# SCH_TEMPEC-CLOUD-SMD_2022-08-11.net
KiCad netlist of a schematic drawn in EasyEDA
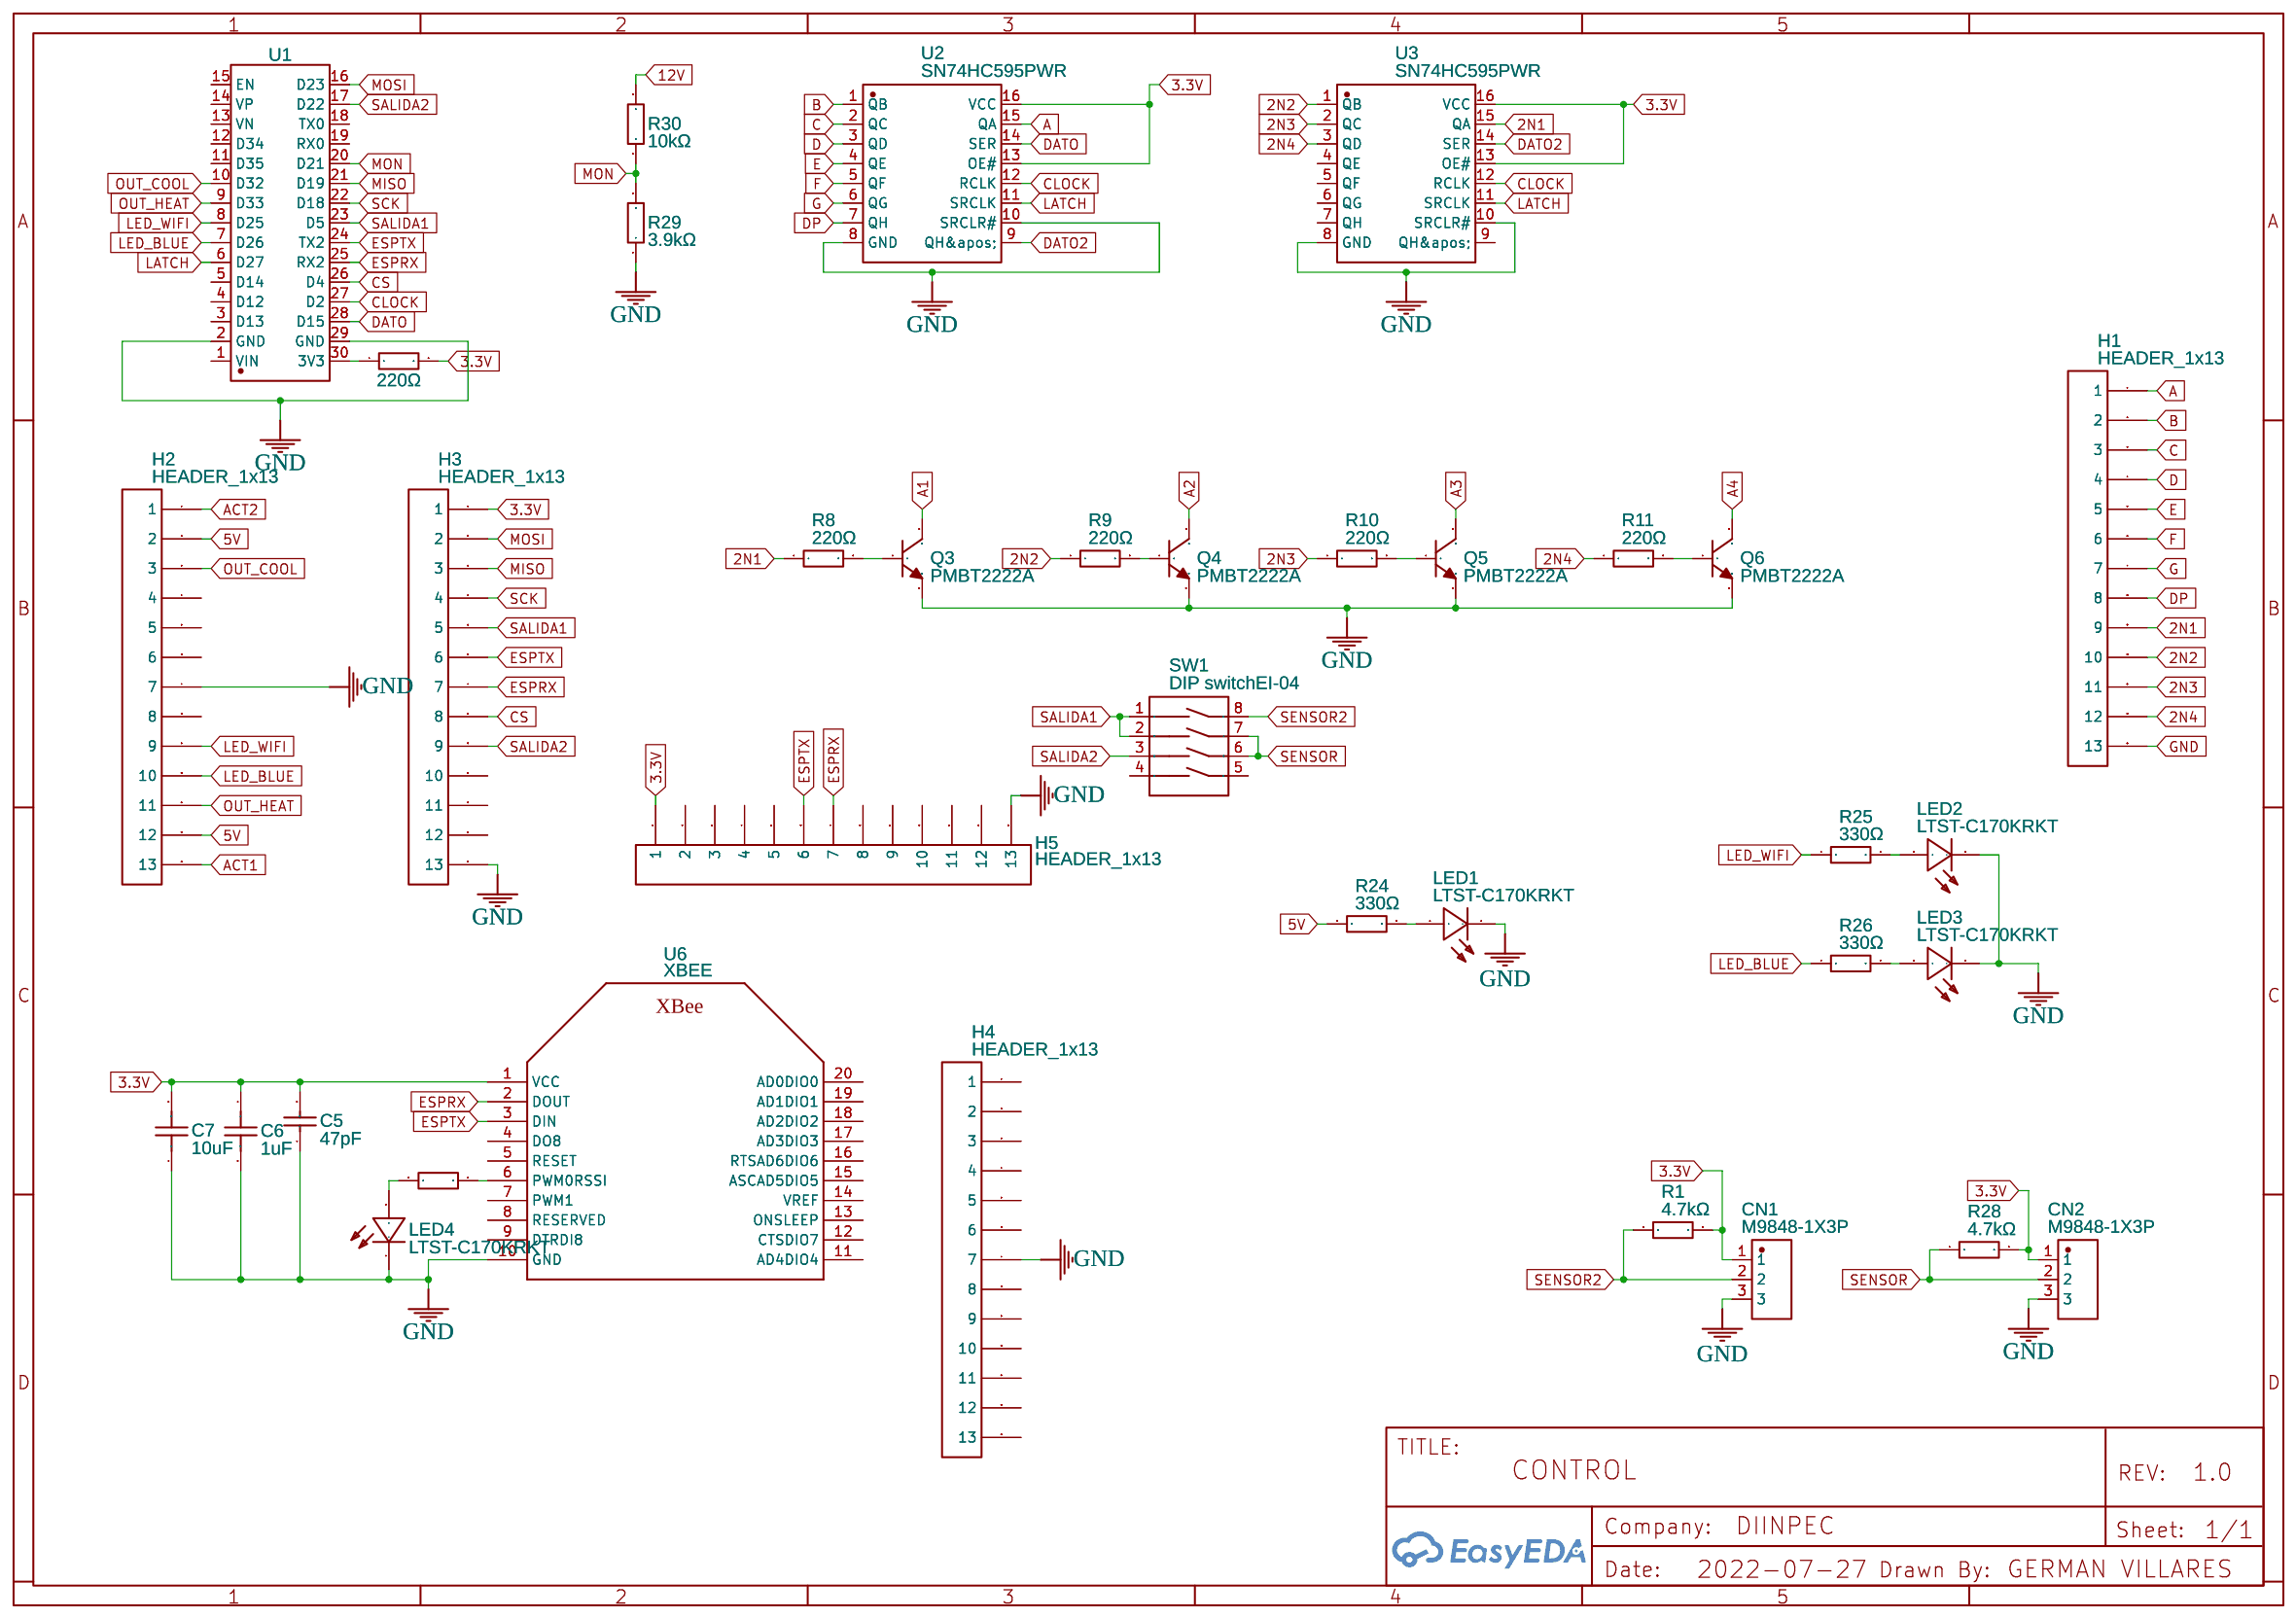
[diagram p0: CONTROL]
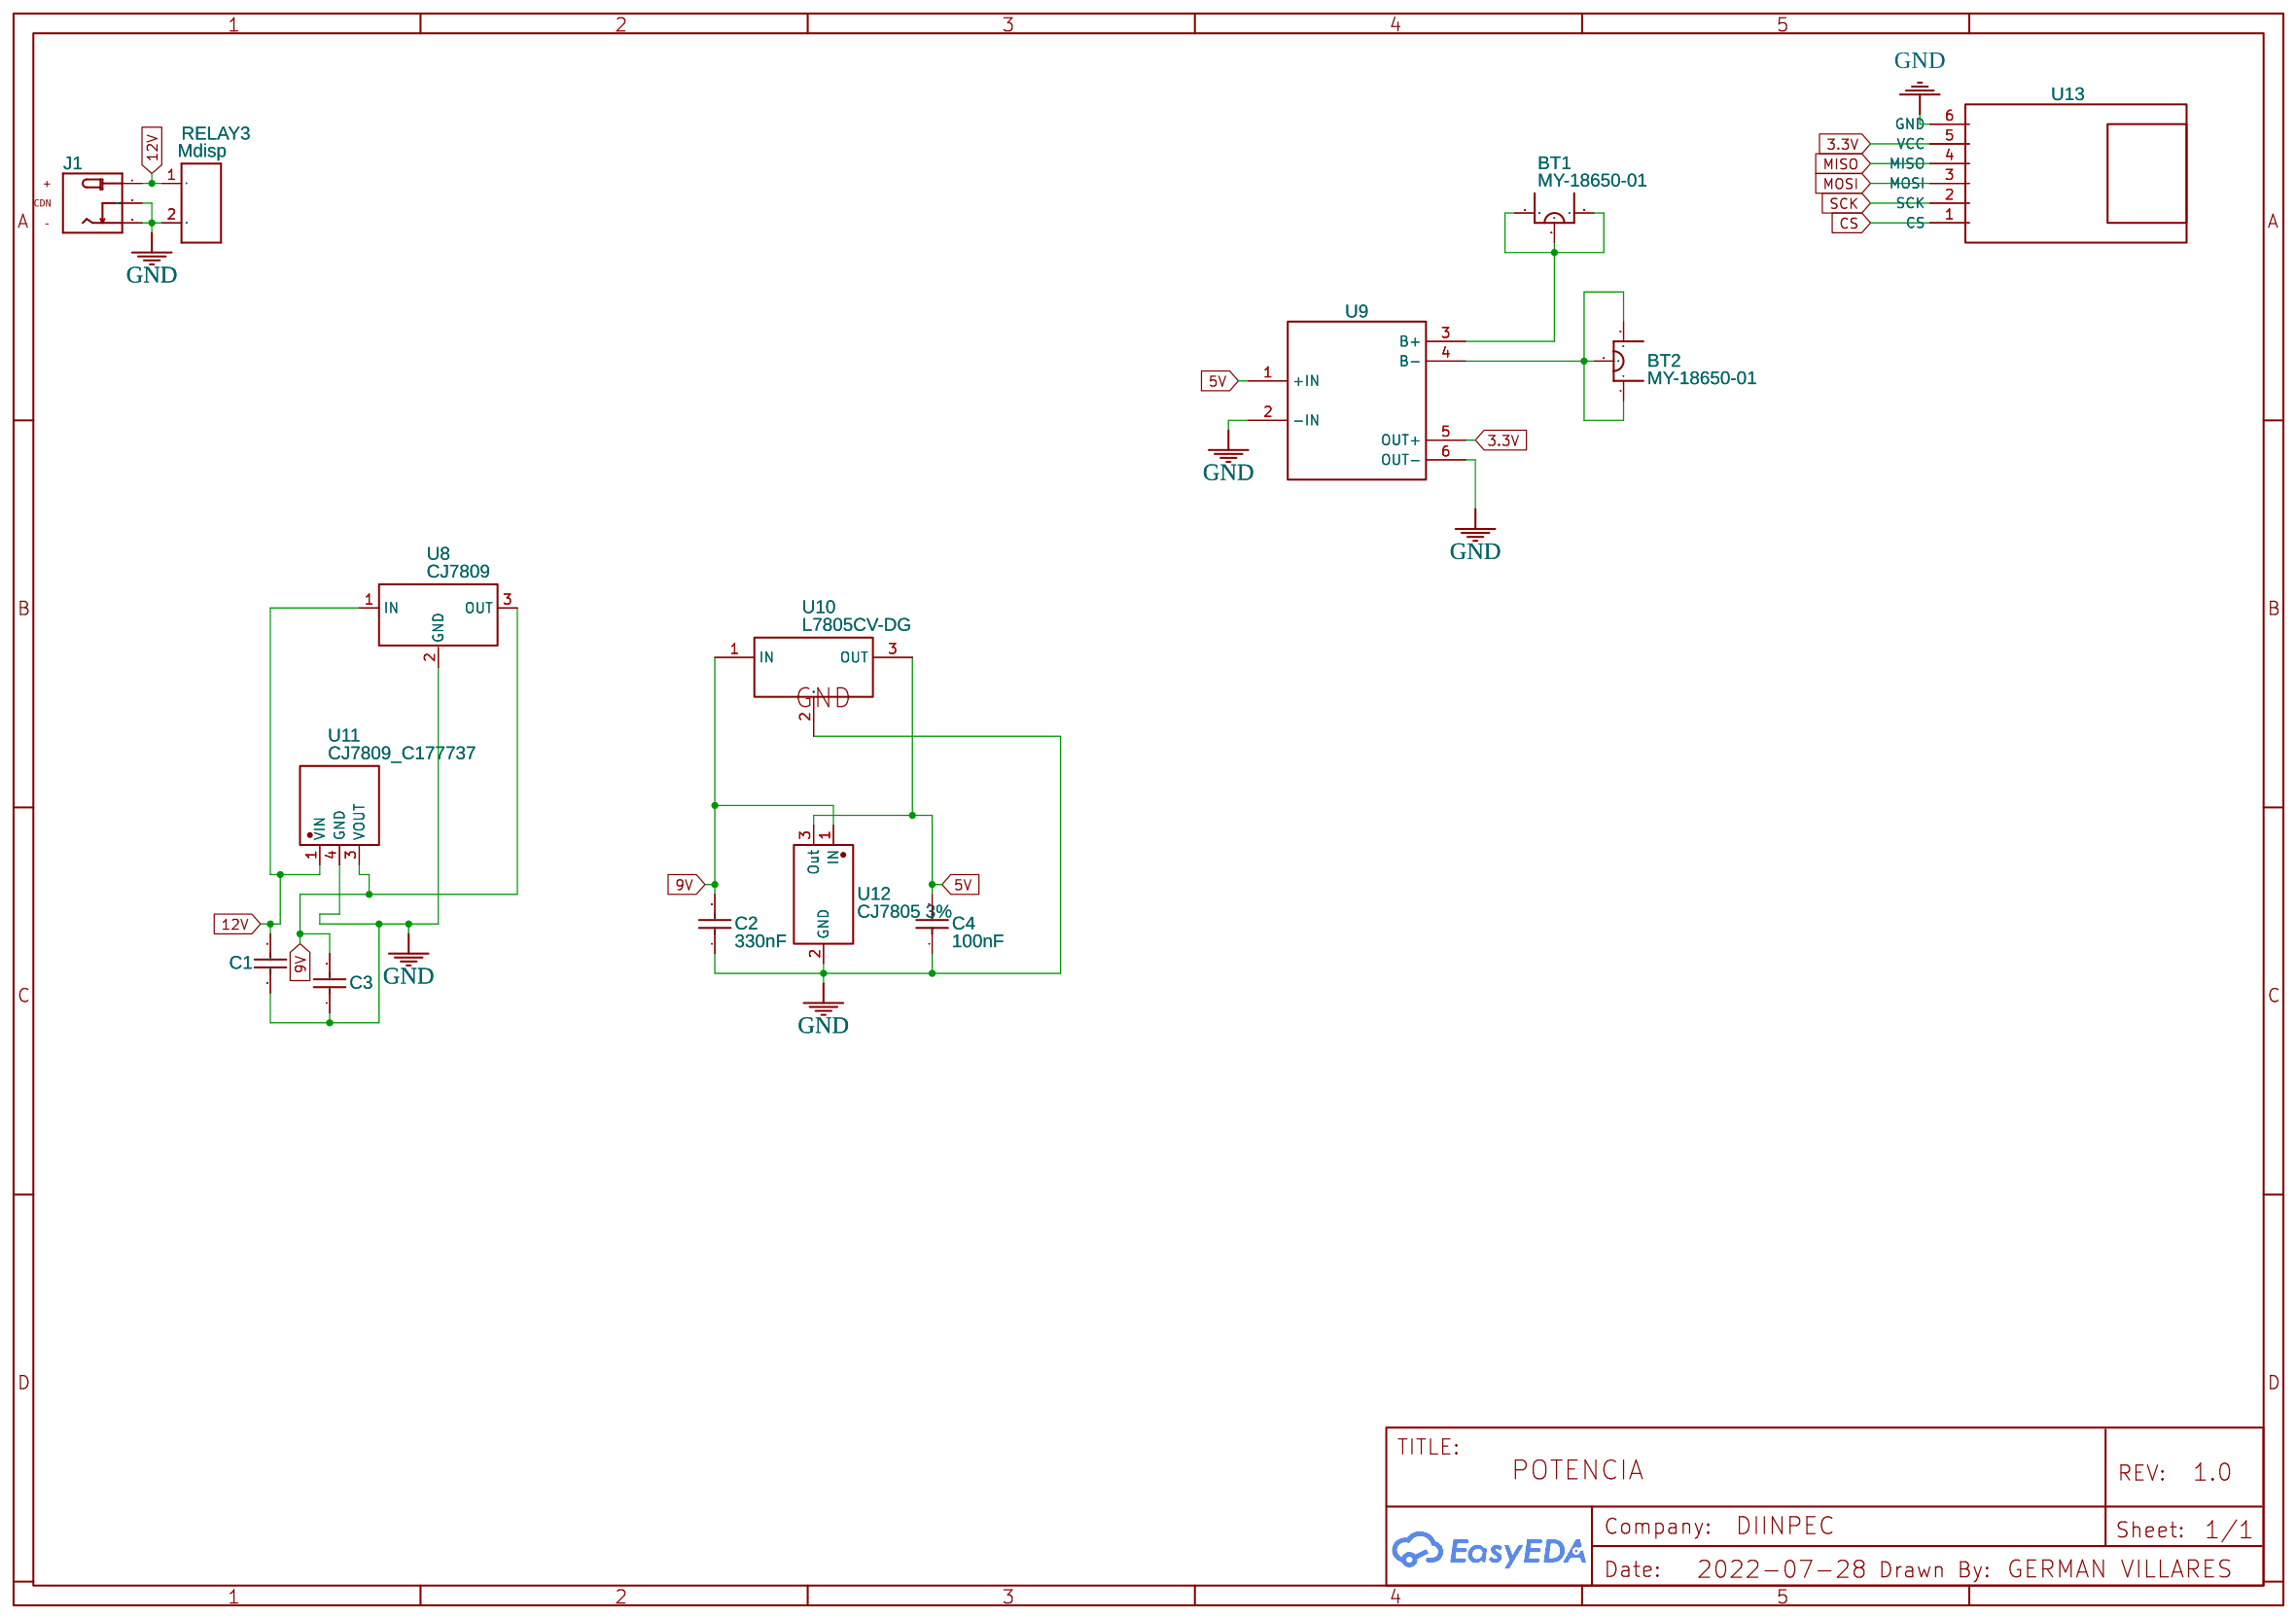
[diagram p1: POTENCIA]
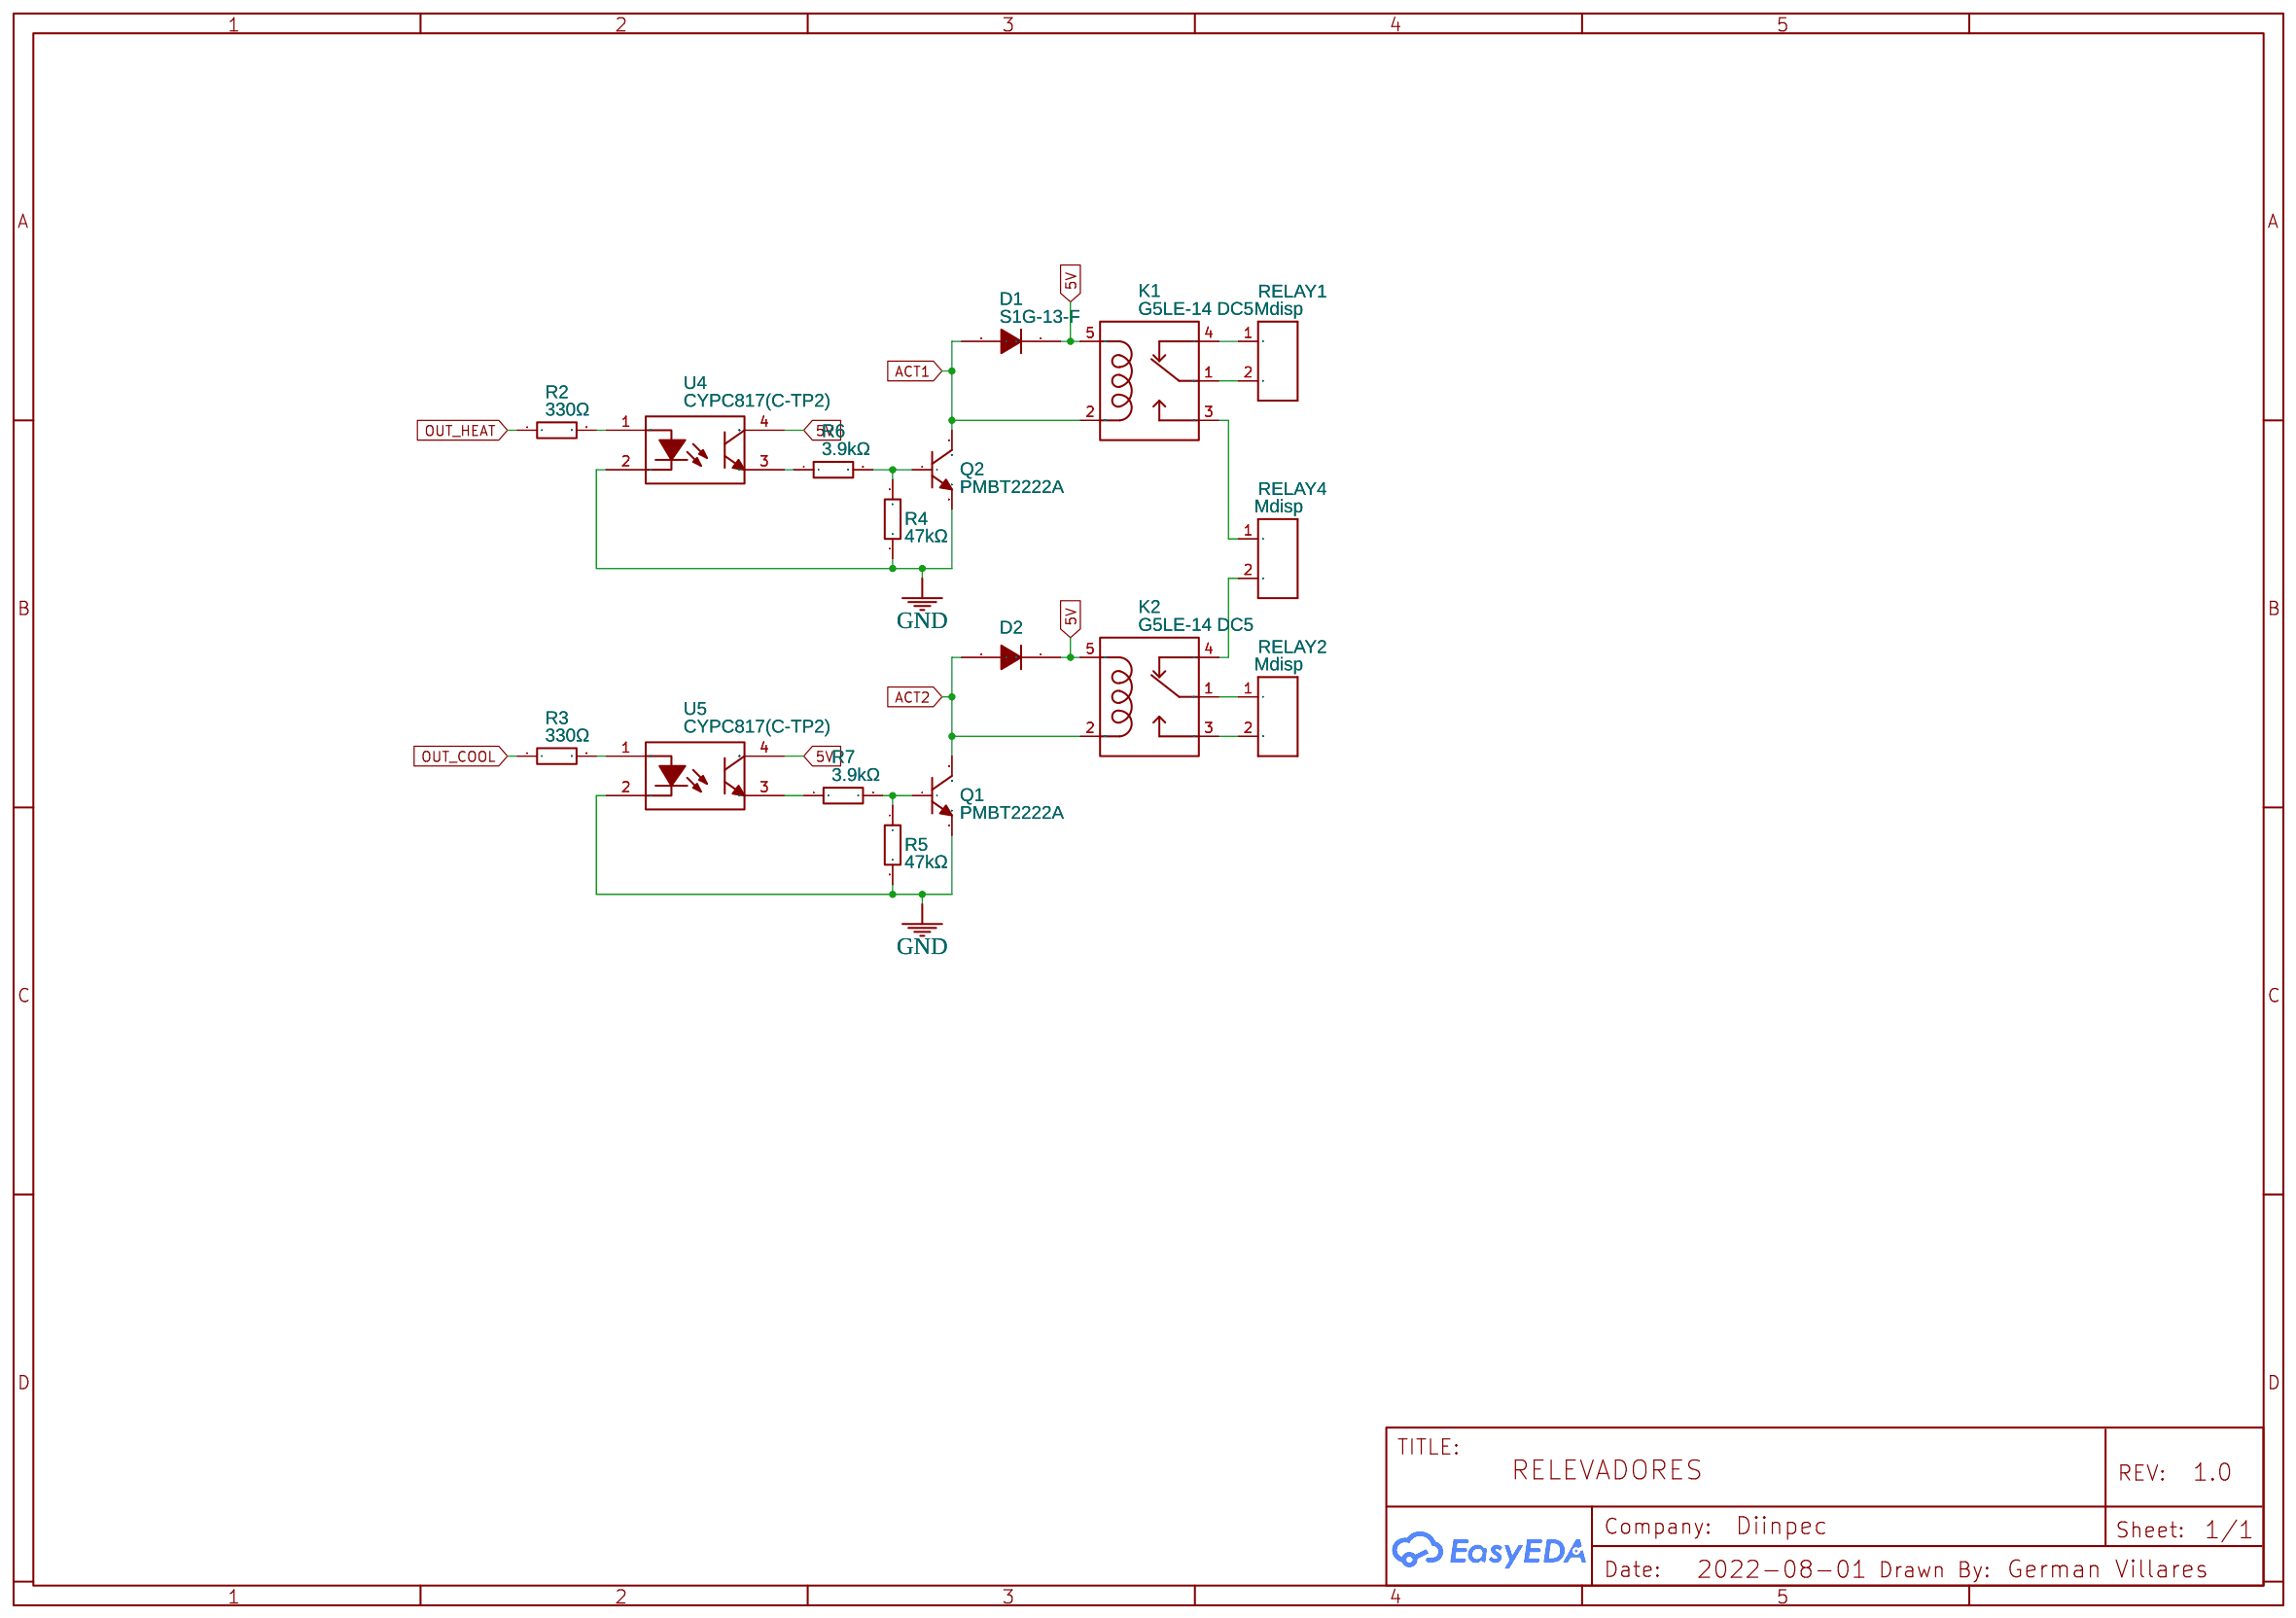
[diagram p2: Relevadores]
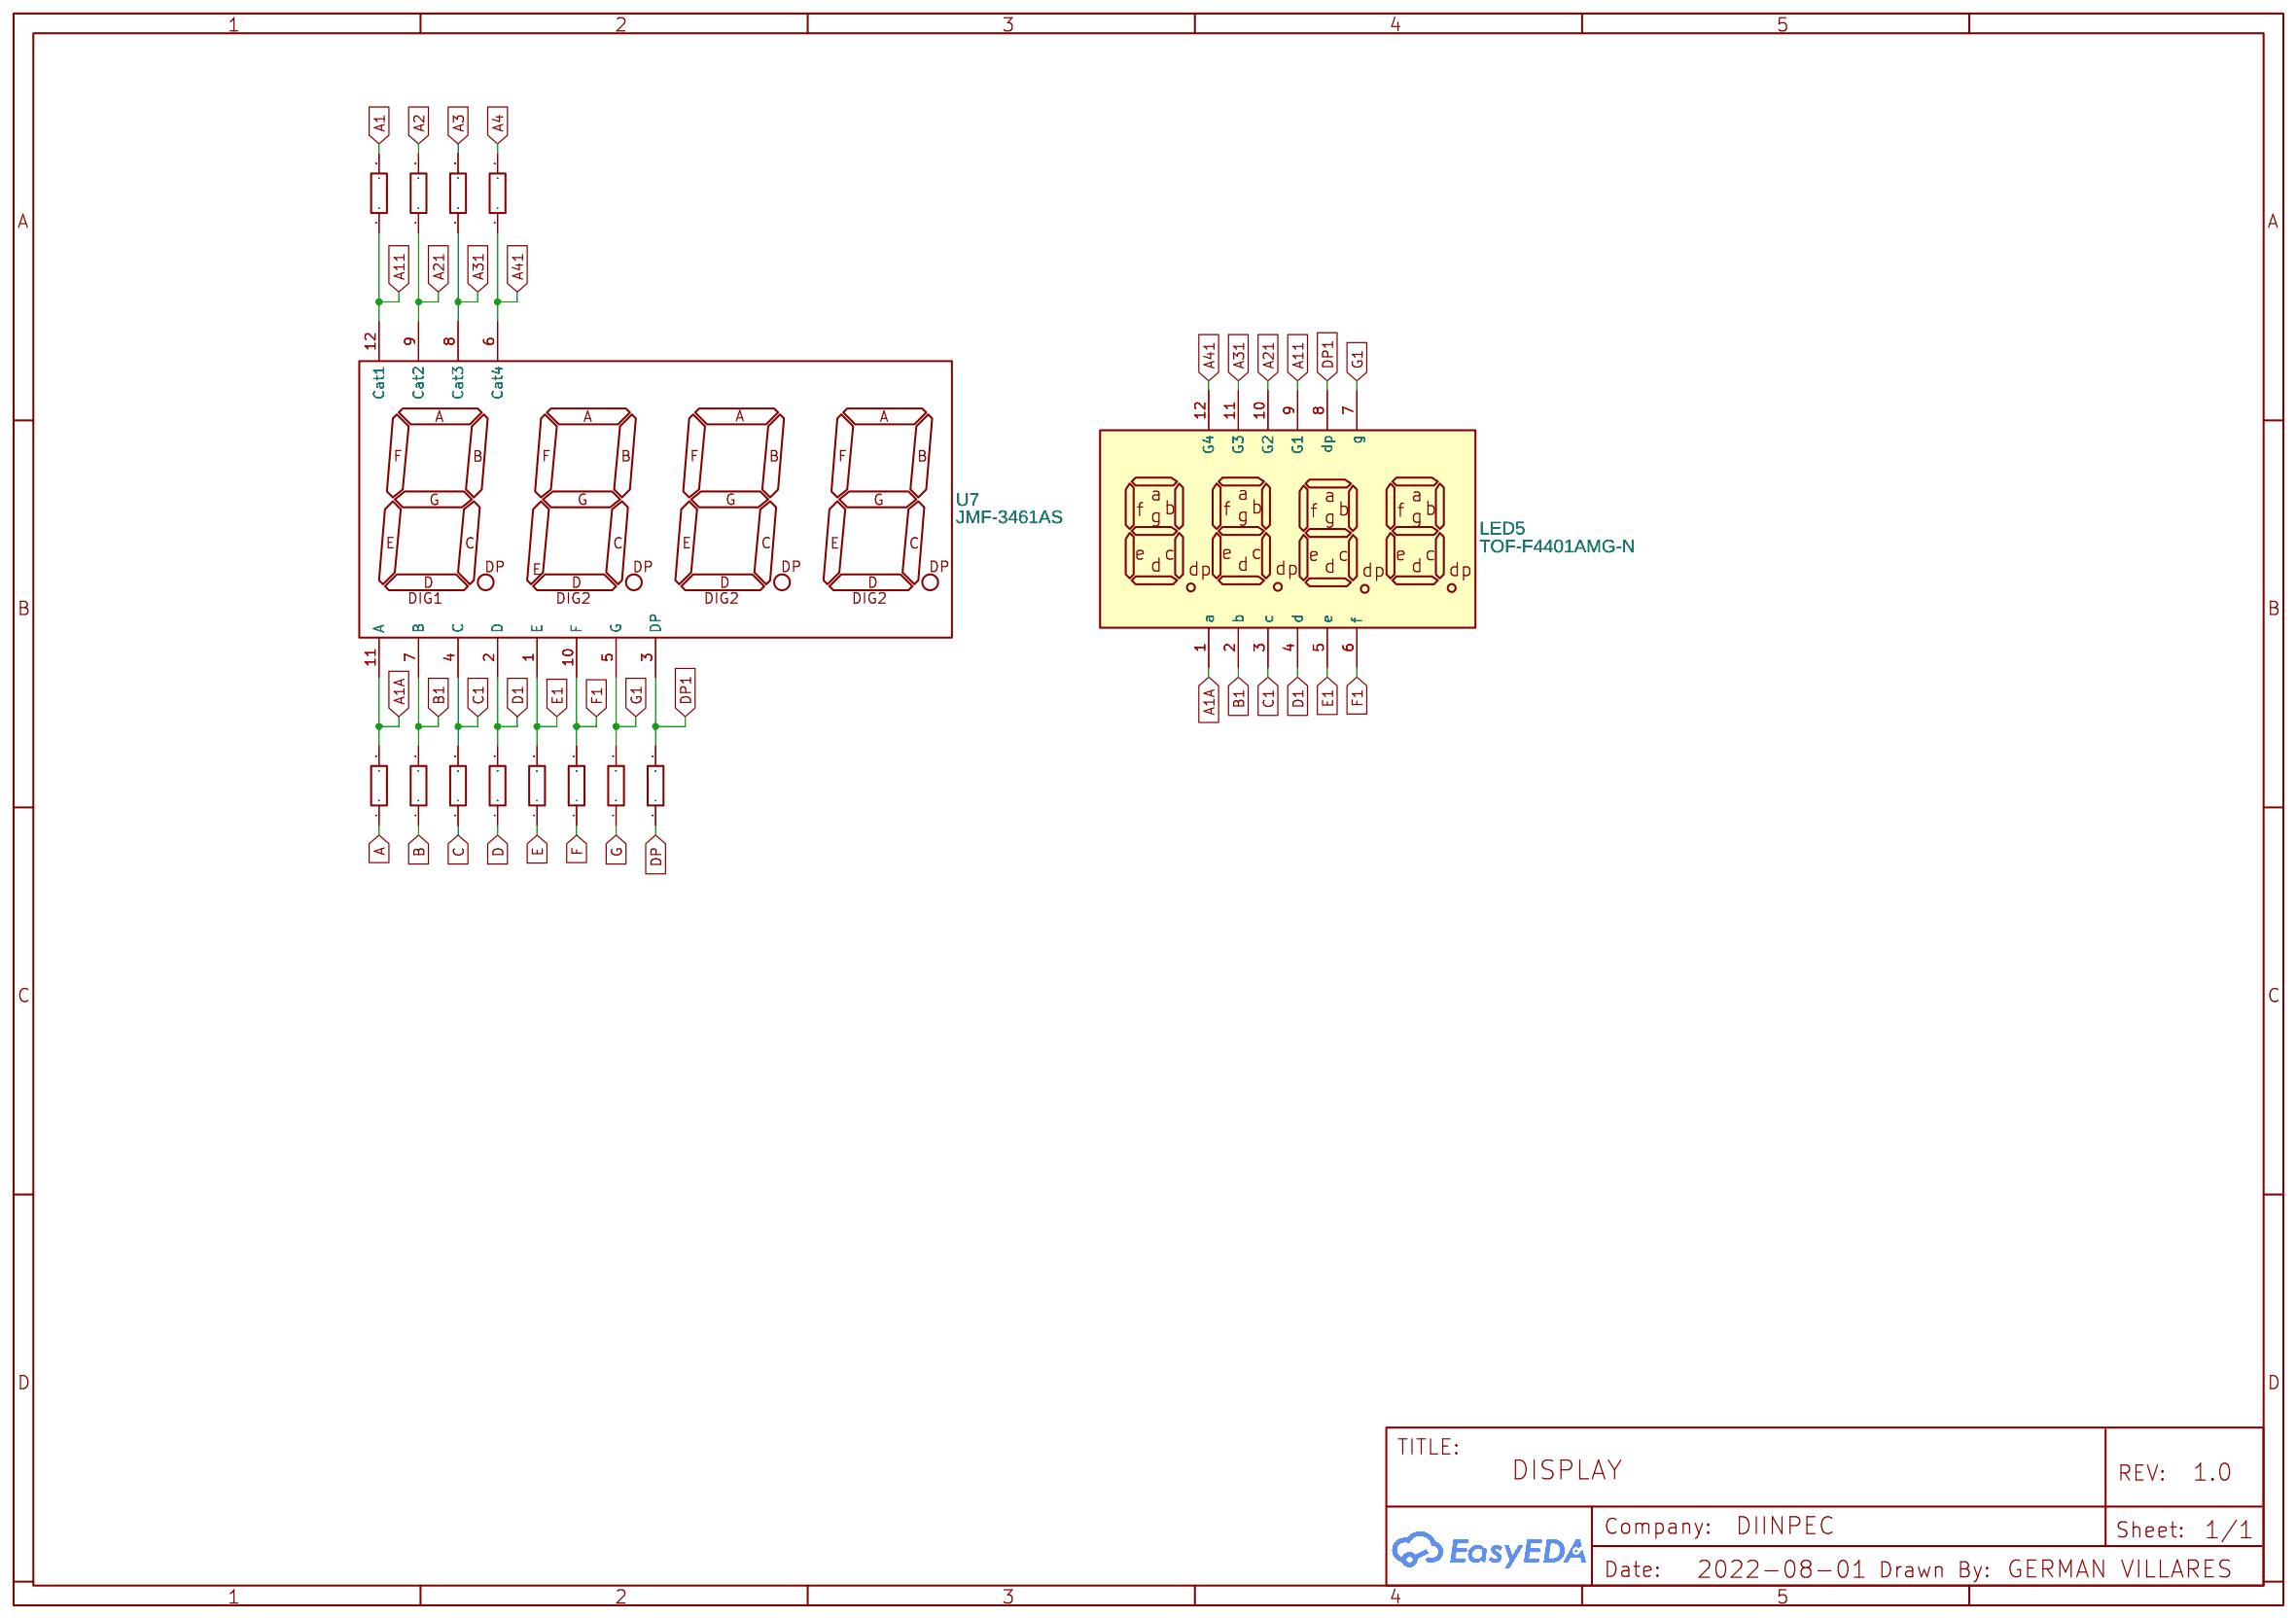
[diagram p3: DISPLAY]

(export (version "E")
  (design (tool "Eeschema 10.0.6"))
  (components
    (comp (ref "C5")
      (value "47pF")
      (fields
        (field (name "BOM_Manufacturer Part") "CC0805JRNPO9BN470")
        (field (name "BOM_Supplier Part") "C107118")
      )
      (libsource (lib "") (part "CC0805JRNPO9BN470"))
    )
    (comp (ref "C6")
      (value "1uF")
      (fields
        (field (name "BOM_Manufacturer Part") "TCC0805X7R105K500DTS")
        (field (name "BOM_Supplier Part") "C344178")
      )
      (libsource (lib "") (part "TCC0805X7R105K500DTS"))
    )
    (comp (ref "C7")
      (value "10uF")
      (fields
        (field (name "BOM_Manufacturer Part") "CL31B106KBHNNNE")
        (field (name "BOM_Supplier Part") "C89632")
      )
      (libsource (lib "") (part "CL31B106KBHNNNE"))
    )
    (comp (ref "CN1")
      (value "M9848-1X3P")
      (fields
        (field (name "BOM_Manufacturer Part") "M9848-1x3P")
        (field (name "BOM_Supplier Part") "C492604")
      )
      (libsource (lib "") (part "M9848-1X3P"))
    )
    (comp (ref "CN2")
      (value "M9848-1X3P")
      (fields
        (field (name "BOM_Manufacturer Part") "M9848-1x3P")
        (field (name "BOM_Supplier Part") "C492604")
      )
      (libsource (lib "") (part "M9848-1X3P"))
    )
    (comp (ref "H1") (value "HEADER_1x13") (libsource (lib "") (part "HEADER_1x13")))
    (comp (ref "H2") (value "HEADER_1x13") (libsource (lib "") (part "HEADER_1x13")))
    (comp (ref "H3") (value "HEADER_1x13") (libsource (lib "") (part "HEADER_1x13")))
    (comp (ref "H4") (value "HEADER_1x13") (libsource (lib "") (part "HEADER_1x13")))
    (comp (ref "H5") (value "HEADER_1x13") (libsource (lib "") (part "HEADER_1x13_1")))
    (comp (ref "LED1")
      (value "LTST-C170KRKT")
      (fields (field (name "BOM_Supplier Part") "C94868"))
      (libsource (lib "") (part "LTST-C170KRKT"))
    )
    (comp (ref "LED2")
      (value "LTST-C170KRKT")
      (fields (field (name "BOM_Supplier Part") "C94868"))
      (libsource (lib "") (part "LTST-C170KRKT"))
    )
    (comp (ref "LED3")
      (value "LTST-C170KRKT")
      (fields (field (name "BOM_Supplier Part") "C94868"))
      (libsource (lib "") (part "LTST-C170KRKT"))
    )
    (comp (ref "LED4")
      (value "LTST-C170KRKT")
      (fields (field (name "BOM_Supplier Part") "C94868"))
      (libsource (lib "") (part "LTST-C170KRKT_1"))
    )
    (comp (ref "Q3")
      (value "PMBT2222A")
      (fields (field (name "BOM_Supplier Part") "C23869"))
      (libsource (lib "") (part "PMBT2222A"))
    )
    (comp (ref "Q4")
      (value "PMBT2222A")
      (fields (field (name "BOM_Supplier Part") "C23869"))
      (libsource (lib "") (part "PMBT2222A"))
    )
    (comp (ref "Q5")
      (value "PMBT2222A")
      (fields (field (name "BOM_Supplier Part") "C23869"))
      (libsource (lib "") (part "PMBT2222A"))
    )
    (comp (ref "Q6")
      (value "PMBT2222A")
      (fields (field (name "BOM_Supplier Part") "C23869"))
      (libsource (lib "") (part "PMBT2222A"))
    )
    (comp (ref "R1")
      (value "4.7kΩ")
      (fields
        (field (name "BOM_Manufacturer Part") "RS-06K472JT")
        (field (name "BOM_Supplier Part") "C118074")
      )
      (libsource (lib "") (part "RS-06K472JT"))
    )
    (comp (ref "R8")
      (value "220Ω")
      (fields
        (field (name "BOM_Manufacturer Part") "CR1206F42200G")
        (field (name "BOM_Supplier Part") "C102128")
      )
      (libsource (lib "") (part "CR1206F42200G"))
    )
    (comp (ref "R9")
      (value "220Ω")
      (fields
        (field (name "BOM_Manufacturer Part") "CR1206F42200G")
        (field (name "BOM_Supplier Part") "C102128")
      )
      (libsource (lib "") (part "CR1206F42200G"))
    )
    (comp (ref "R10")
      (value "220Ω")
      (fields
        (field (name "BOM_Manufacturer Part") "CR1206F42200G")
        (field (name "BOM_Supplier Part") "C102128")
      )
      (libsource (lib "") (part "CR1206F42200G"))
    )
    (comp (ref "R11")
      (value "220Ω")
      (fields
        (field (name "BOM_Manufacturer Part") "CR1206F42200G")
        (field (name "BOM_Supplier Part") "C102128")
      )
      (libsource (lib "") (part "CR1206F42200G"))
    )
    (comp (ref "R24")
      (value "330Ω")
      (fields
        (field (name "BOM_Manufacturer Part") "1206W4F3300T5E")
        (field (name "BOM_Supplier Part") "C17930")
      )
      (libsource (lib "") (part "1206W4F3300T5E"))
    )
    (comp (ref "R25")
      (value "330Ω")
      (fields
        (field (name "BOM_Manufacturer Part") "1206W4F3300T5E")
        (field (name "BOM_Supplier Part") "C17930")
      )
      (libsource (lib "") (part "1206W4F3300T5E"))
    )
    (comp (ref "R26")
      (value "330Ω")
      (fields
        (field (name "BOM_Manufacturer Part") "1206W4F3300T5E")
        (field (name "BOM_Supplier Part") "C17930")
      )
      (libsource (lib "") (part "1206W4F3300T5E"))
    )
    (comp (ref "R27")
      (value "220Ω")
      (fields
        (field (name "BOM_Manufacturer Part") "CR1206F42200G")
        (field (name "BOM_Supplier Part") "C102128")
      )
      (libsource (lib "") (part "CR1206F42200G"))
    )
    (comp (ref "R28")
      (value "4.7kΩ")
      (fields
        (field (name "BOM_Manufacturer Part") "RS-06K472JT")
        (field (name "BOM_Supplier Part") "C118074")
      )
      (libsource (lib "") (part "RS-06K472JT"))
    )
    (comp (ref "R29")
      (value "3.9kΩ")
      (fields
        (field (name "BOM_Manufacturer Part") "RMC12063.9K5%N")
        (field (name "BOM_Supplier Part") "C269606")
      )
      (libsource (lib "") (part "RMC12063.9K5%N"))
    )
    (comp (ref "R30")
      (value "10kΩ")
      (fields
        (field (name "BOM_Manufacturer Part") "RTT061002FTP")
        (field (name "BOM_Supplier Part") "C104595")
      )
      (libsource (lib "") (part "RTT061002FTP"))
    )
    (comp (ref "R31")
      (value "330Ω")
      (fields
        (field (name "BOM_Manufacturer Part") "1206W4F3300T5E")
        (field (name "BOM_Supplier Part") "C17930")
      )
      (libsource (lib "") (part "1206W4F3300T5E_1"))
    )
    (comp (ref "SW1")
      (value "DIP switchEI-04")
      (fields (field (name "BOM_Supplier Part") "C99987"))
      (libsource (lib "") (part "DIP switchEI-04"))
    )
    (comp (ref "U1")
      (value "ESP32-WROOM-32-DEV KIT C")
      (libsource (lib "") (part "ESP32-WROOM-32-DEV KIT C"))
    )
    (comp (ref "U2")
      (value "SN74HC595PWR")
      (fields (field (name "BOM_Supplier Part") "C273642"))
      (libsource (lib "") (part "SN74HC595PWR"))
    )
    (comp (ref "U3")
      (value "SN74HC595PWR")
      (fields (field (name "BOM_Supplier Part") "C273642"))
      (libsource (lib "") (part "SN74HC595PWR"))
    )
    (comp (ref "U6") (value "XBEE") (libsource (lib "") (part "Unknown_335_-240")))
    (comp (ref "BT1")
      (value "MY-18650-01")
      (fields (field (name "BOM_Supplier Part") "C2979183"))
      (libsource (lib "") (part "MY-18650-01_1"))
    )
    (comp (ref "BT2")
      (value "MY-18650-01")
      (fields (field (name "BOM_Supplier Part") "C2979183"))
      (libsource (lib "") (part "MY-18650-01"))
    )
    (comp (ref "C1")
      (value "330nF")
      (fields
        (field (name "BOM_Manufacturer Part") "0805F334M500NT")
        (field (name "BOM_Supplier Part") "C1775")
      )
      (libsource (lib "") (part "0805F334M500NT"))
    )
    (comp (ref "C2")
      (value "330nF")
      (fields
        (field (name "BOM_Manufacturer Part") "0805F334M500NT")
        (field (name "BOM_Supplier Part") "C1775")
      )
      (libsource (lib "") (part "0805F334M500NT"))
    )
    (comp (ref "C3")
      (value "100nF")
      (fields
        (field (name "BOM_Manufacturer Part") "CL21B104JBCNNNC")
        (field (name "BOM_Supplier Part") "C62912")
      )
      (libsource (lib "") (part "CL21B104JBCNNNC"))
    )
    (comp (ref "C4")
      (value "100nF")
      (fields
        (field (name "BOM_Manufacturer Part") "CL21B104JBCNNNC")
        (field (name "BOM_Supplier Part") "C62912")
      )
      (libsource (lib "") (part "CL21B104JBCNNNC"))
    )
    (comp (ref "J1")
      (value "CONN-POWER-JACK-2.1MM_DC-005_")
      (libsource (lib "") (part "CONN-POWER-JACK-2.1MM_DC-005_"))
    )
    (comp (ref "RELAY3")
      (value "Mdisp")
      (fields (field (name "BOM_Manufacturer Part") "?"))
      (libsource (lib "") (part "Unknown_90_-710"))
    )
    (comp (ref "U8")
      (value "CJ7809")
      (fields (field (name "BOM_Supplier Part") "C105445"))
      (libsource (lib "") (part "CJ7809"))
    )
    (comp (ref "U9") (value "TP4056 MODULE D0") (libsource (lib "") (part "TP4056 MODULE D0")))
    (comp (ref "U10")
      (value "L7805CV-DG")
      (fields (field (name "BOM_Supplier Part") "C3795"))
      (libsource (lib "") (part "L7805CV-DG"))
    )
    (comp (ref "U11")
      (value "CJ7809_C177737")
      (fields (field (name "BOM_Manufacturer Part") "CJ7809") (field (name "BOM_Supplier Part") "C177737"))
      (libsource (lib "") (part "CJ7809_C177737"))
    )
    (comp (ref "U12")
      (value "CJ7805 3%")
      (fields (field (name "BOM_Supplier Part") "C21706"))
      (libsource (lib "") (part "CJ7805 3%"))
    )
    (comp (ref "U13") (value "MicroSDCardAdapter") (libsource (lib "") (part "MicroSDCardAdapter")))
    (comp (ref "D1")
      (value "S1G-13-F")
      (fields (field (name "BOM_Supplier Part") "C85102"))
      (libsource (lib "") (part "S1G-13-F"))
    )
    (comp (ref "D2")
      (value "S1G-13-F")
      (fields (field (name "BOM_Supplier Part") "C85102"))
      (libsource (lib "") (part "S1G-13-F"))
    )
    (comp (ref "K1")
      (value "G5LE-14 DC5")
      (fields (field (name "BOM_Supplier Part") "C152709"))
      (libsource (lib "") (part "Unknown_580_-620"))
    )
    (comp (ref "K2")
      (value "G5LE-14 DC5")
      (fields (field (name "BOM_Supplier Part") "C152709"))
      (libsource (lib "") (part "Unknown_580_-460"))
    )
    (comp (ref "Q1")
      (value "PMBT2222A")
      (fields (field (name "BOM_Supplier Part") "C23869"))
      (libsource (lib "") (part "PMBT2222A"))
    )
    (comp (ref "Q2")
      (value "PMBT2222A")
      (fields (field (name "BOM_Supplier Part") "C23869"))
      (libsource (lib "") (part "PMBT2222A"))
    )
    (comp (ref "R2")
      (value "330Ω")
      (fields
        (field (name "BOM_Manufacturer Part") "1206W4F3300T5E")
        (field (name "BOM_Supplier Part") "C17930")
      )
      (libsource (lib "") (part "1206W4F3300T5E"))
    )
    (comp (ref "R3")
      (value "330Ω")
      (fields
        (field (name "BOM_Manufacturer Part") "1206W4F3300T5E")
        (field (name "BOM_Supplier Part") "C17930")
      )
      (libsource (lib "") (part "1206W4F3300T5E"))
    )
    (comp (ref "R4")
      (value "47kΩ")
      (fields
        (field (name "BOM_Manufacturer Part") "RTT06473JTP")
        (field (name "BOM_Supplier Part") "C104822")
      )
      (libsource (lib "") (part "RTT06473JTP"))
    )
    (comp (ref "R5")
      (value "47kΩ")
      (fields
        (field (name "BOM_Manufacturer Part") "RTT06473JTP")
        (field (name "BOM_Supplier Part") "C104822")
      )
      (libsource (lib "") (part "RTT06473JTP_1"))
    )
    (comp (ref "R6")
      (value "3.9kΩ")
      (fields
        (field (name "BOM_Manufacturer Part") "RMC12063.9K5%N")
        (field (name "BOM_Supplier Part") "C269606")
      )
      (libsource (lib "") (part "RMC12063.9K5%N"))
    )
    (comp (ref "R7")
      (value "3.9kΩ")
      (fields
        (field (name "BOM_Manufacturer Part") "RMC12063.9K5%N")
        (field (name "BOM_Supplier Part") "C269606")
      )
      (libsource (lib "") (part "RMC12063.9K5%N"))
    )
    (comp (ref "RELAY1")
      (value "Mdisp")
      (fields (field (name "BOM_Manufacturer Part") "?"))
      (libsource (lib "") (part "Unknown_635_-630"))
    )
    (comp (ref "RELAY2")
      (value "Mdisp")
      (fields (field (name "BOM_Manufacturer Part") "?"))
      (libsource (lib "") (part "Unknown_635_-450"))
    )
    (comp (ref "RELAY4")
      (value "Mdisp")
      (fields (field (name "BOM_Manufacturer Part") "?"))
      (libsource (lib "") (part "Unknown_635_-530"))
    )
    (comp (ref "U4")
      (value "CYPC817(C-TP2)")
      (fields (field (name "BOM_Supplier Part") "C385058"))
      (libsource (lib "") (part "CYPC817(C-TP2)"))
    )
    (comp (ref "U5")
      (value "CYPC817(C-TP2)")
      (fields (field (name "BOM_Supplier Part") "C385058"))
      (libsource (lib "") (part "CYPC817(C-TP2)"))
    )
    (comp (ref "LED5")
      (value "TOF-F4401AMG-N")
      (fields (field (name "BOM_Supplier Part") "C325426"))
      (libsource (lib "") (part "TOF-F4401AMG-N"))
    )
    (comp (ref "R12")
      (value "220Ω")
      (fields
        (field (name "BOM_Manufacturer Part") "AECR1206F220RK9")
        (field (name "BOM_Supplier Part") "C352117")
      )
      (libsource (lib "") (part "AECR1206F220RK9"))
    )
    (comp (ref "R13")
      (value "220Ω")
      (fields
        (field (name "BOM_Manufacturer Part") "AECR1206F220RK9")
        (field (name "BOM_Supplier Part") "C352117")
      )
      (libsource (lib "") (part "AECR1206F220RK9"))
    )
    (comp (ref "R14")
      (value "220Ω")
      (fields
        (field (name "BOM_Manufacturer Part") "AECR1206F220RK9")
        (field (name "BOM_Supplier Part") "C352117")
      )
      (libsource (lib "") (part "AECR1206F220RK9"))
    )
    (comp (ref "R15")
      (value "220Ω")
      (fields
        (field (name "BOM_Manufacturer Part") "AECR1206F220RK9")
        (field (name "BOM_Supplier Part") "C352117")
      )
      (libsource (lib "") (part "AECR1206F220RK9"))
    )
    (comp (ref "R16")
      (value "220Ω")
      (fields
        (field (name "BOM_Manufacturer Part") "AECR1206F220RK9")
        (field (name "BOM_Supplier Part") "C352117")
      )
      (libsource (lib "") (part "AECR1206F220RK9"))
    )
    (comp (ref "R17")
      (value "220Ω")
      (fields
        (field (name "BOM_Manufacturer Part") "AECR1206F220RK9")
        (field (name "BOM_Supplier Part") "C352117")
      )
      (libsource (lib "") (part "AECR1206F220RK9"))
    )
    (comp (ref "R18")
      (value "220Ω")
      (fields
        (field (name "BOM_Manufacturer Part") "AECR1206F220RK9")
        (field (name "BOM_Supplier Part") "C352117")
      )
      (libsource (lib "") (part "AECR1206F220RK9"))
    )
    (comp (ref "R19")
      (value "220Ω")
      (fields
        (field (name "BOM_Manufacturer Part") "AECR1206F220RK9")
        (field (name "BOM_Supplier Part") "C352117")
      )
      (libsource (lib "") (part "AECR1206F220RK9"))
    )
    (comp (ref "R20")
      (value "220Ω")
      (fields
        (field (name "BOM_Manufacturer Part") "AECR1206F220RK9")
        (field (name "BOM_Supplier Part") "C352117")
      )
      (libsource (lib "") (part "AECR1206F220RK9"))
    )
    (comp (ref "R21")
      (value "220Ω")
      (fields
        (field (name "BOM_Manufacturer Part") "AECR1206F220RK9")
        (field (name "BOM_Supplier Part") "C352117")
      )
      (libsource (lib "") (part "AECR1206F220RK9"))
    )
    (comp (ref "R22")
      (value "220Ω")
      (fields
        (field (name "BOM_Manufacturer Part") "AECR1206F220RK9")
        (field (name "BOM_Supplier Part") "C352117")
      )
      (libsource (lib "") (part "AECR1206F220RK9"))
    )
    (comp (ref "R23")
      (value "220Ω")
      (fields
        (field (name "BOM_Manufacturer Part") "AECR1206F220RK9")
        (field (name "BOM_Supplier Part") "C352117")
      )
      (libsource (lib "") (part "AECR1206F220RK9"))
    )
    (comp (ref "U7")
      (value "JMF-3461AS")
      (fields (field (name "BOM_Manufacturer Part") "3461AS"))
      (libsource (lib "") (part "JMF-3461AS"))
    )
  )
  (nets
    (net (code "1") (name "2N1") (class "Default")
      (node (ref "H1") (pin "9") (pinfunction "9_9") (pintype "unspecified"))
      (node (ref "R8") (pin "1") (pinfunction "1_1") (pintype "input"))
      (node (ref "U3") (pin "15") (pinfunction "QA_15") (pintype "unspecified"))
    )
    (net (code "2") (name "2N2") (class "Default")
      (node (ref "H1") (pin "10") (pinfunction "10_10") (pintype "unspecified"))
      (node (ref "R9") (pin "1") (pinfunction "1_1") (pintype "input"))
      (node (ref "U3") (pin "1") (pinfunction "QB_1") (pintype "unspecified"))
    )
    (net (code "3") (name "2N3") (class "Default")
      (node (ref "H1") (pin "11") (pinfunction "11_11") (pintype "unspecified"))
      (node (ref "R10") (pin "1") (pinfunction "1_1") (pintype "input"))
      (node (ref "U3") (pin "2") (pinfunction "QC_2") (pintype "unspecified"))
    )
    (net (code "4") (name "2N4") (class "Default")
      (node (ref "H1") (pin "12") (pinfunction "12_12") (pintype "unspecified"))
      (node (ref "R11") (pin "1") (pinfunction "1_1") (pintype "input"))
      (node (ref "U3") (pin "3") (pinfunction "QD_3") (pintype "unspecified"))
    )
    (net (code "5") (name "3.3V") (class "Default")
      (node (ref "C5") (pin "2") (pinfunction "2_2") (pintype "input"))
      (node (ref "C6") (pin "1") (pinfunction "1_1") (pintype "unspecified"))
      (node (ref "C7") (pin "2") (pinfunction "2_2") (pintype "unspecified"))
      (node (ref "CN1") (pin "1") (pinfunction "1_1") (pintype "unspecified"))
      (node (ref "CN2") (pin "1") (pinfunction "1_1") (pintype "unspecified"))
      (node (ref "H3") (pin "1") (pinfunction "1_1") (pintype "unspecified"))
      (node (ref "H5") (pin "1") (pinfunction "1_1") (pintype "unspecified"))
      (node (ref "R1") (pin "2") (pinfunction "2_2") (pintype "input"))
      (node (ref "R27") (pin "2") (pinfunction "2_2") (pintype "input"))
      (node (ref "R28") (pin "2") (pinfunction "2_2") (pintype "input"))
      (node (ref "U13") (pin "5") (pinfunction "VCC_5") (pintype "unspecified"))
      (node (ref "U2") (pin "13") (pinfunction "OE#_13") (pintype "unspecified"))
      (node (ref "U2") (pin "16") (pinfunction "VCC_16") (pintype "unspecified"))
      (node (ref "U3") (pin "13") (pinfunction "OE#_13") (pintype "unspecified"))
      (node (ref "U3") (pin "16") (pinfunction "VCC_16") (pintype "unspecified"))
      (node (ref "U6") (pin "1") (pinfunction "VCC_1") (pintype "unspecified"))
      (node (ref "U9") (pin "5") (pinfunction "OUT+_5") (pintype "unspecified"))
    )
    (net (code "6") (name "5V") (class "Default")
      (node (ref "C4") (pin "2") (pinfunction "2_2") (pintype "input"))
      (node (ref "D1") (pin "1") (pinfunction "C_1") (pintype "unspecified"))
      (node (ref "D2") (pin "1") (pinfunction "C_1") (pintype "unspecified"))
      (node (ref "H2") (pin "12") (pinfunction "12_12") (pintype "unspecified"))
      (node (ref "H2") (pin "2") (pinfunction "2_2") (pintype "unspecified"))
      (node (ref "K1") (pin "5") (pinfunction "COIL1_5") (pintype "unspecified"))
      (node (ref "K2") (pin "5") (pinfunction "COIL1_5") (pintype "unspecified"))
      (node (ref "R24") (pin "1") (pinfunction "1_1") (pintype "input"))
      (node (ref "U10") (pin "3") (pinfunction "OUT_3") (pintype "passive"))
      (node (ref "U12") (pin "3") (pinfunction "Out_3") (pintype "unspecified"))
      (node (ref "U4") (pin "4") (pinfunction "COL_4") (pintype "unspecified"))
      (node (ref "U5") (pin "4") (pinfunction "COL_4") (pintype "unspecified"))
      (node (ref "U9") (pin "1") (pinfunction "+IN_1") (pintype "unspecified"))
    )
    (net (code "7") (name "9V") (class "Default")
      (node (ref "C2") (pin "2") (pinfunction "2_2") (pintype "input"))
      (node (ref "C3") (pin "2") (pinfunction "2_2") (pintype "input"))
      (node (ref "U10") (pin "1") (pinfunction "IN_1") (pintype "passive"))
      (node (ref "U11") (pin "3") (pinfunction "VOUT_3") (pintype "unspecified"))
      (node (ref "U12") (pin "1") (pinfunction "IN_1") (pintype "unspecified"))
      (node (ref "U8") (pin "3") (pinfunction "OUT_3") (pintype "unspecified"))
    )
    (net (code "8") (name "12V") (class "Default")
      (node (ref "C1") (pin "2") (pinfunction "2_2") (pintype "input"))
      (node (ref "J1") (pin "1") (pinfunction "+_1") (pintype "bidirectional"))
      (node (ref "R30") (pin "2") (pinfunction "2_2") (pintype "input"))
      (node (ref "RELAY3") (pin "1") (pinfunction "1_1") (pintype "unspecified"))
      (node (ref "U11") (pin "1") (pinfunction "VIN_1") (pintype "unspecified"))
      (node (ref "U8") (pin "1") (pinfunction "IN_1") (pintype "unspecified"))
    )
    (net (code "9") (name "A") (class "Default")
      (node (ref "H1") (pin "1") (pinfunction "1_1") (pintype "unspecified"))
      (node (ref "R12") (pin "1") (pinfunction "1_1") (pintype "unspecified"))
      (node (ref "U2") (pin "15") (pinfunction "QA_15") (pintype "unspecified"))
    )
    (net (code "10") (name "A1") (class "Default")
      (node (ref "Q3") (pin "3") (pinfunction "3_3") (pintype "input"))
      (node (ref "R20") (pin "2") (pinfunction "2_2") (pintype "unspecified"))
    )
    (net (code "11") (name "A1A") (class "Default")
      (node (ref "LED5") (pin "1") (pinfunction "a_1") (pintype "input"))
      (node (ref "R12") (pin "2") (pinfunction "2_2") (pintype "unspecified"))
      (node (ref "U7") (pin "11") (pinfunction "A_11") (pintype "unspecified"))
    )
    (net (code "12") (name "A2") (class "Default")
      (node (ref "Q4") (pin "3") (pinfunction "3_3") (pintype "input"))
      (node (ref "R21") (pin "2") (pinfunction "2_2") (pintype "unspecified"))
    )
    (net (code "13") (name "A3") (class "Default")
      (node (ref "Q5") (pin "3") (pinfunction "3_3") (pintype "input"))
      (node (ref "R22") (pin "2") (pinfunction "2_2") (pintype "unspecified"))
    )
    (net (code "14") (name "A4") (class "Default")
      (node (ref "Q6") (pin "3") (pinfunction "3_3") (pintype "input"))
      (node (ref "R23") (pin "2") (pinfunction "2_2") (pintype "unspecified"))
    )
    (net (code "15") (name "A11") (class "Default")
      (node (ref "LED5") (pin "9") (pinfunction "G1_9") (pintype "input"))
      (node (ref "R20") (pin "1") (pinfunction "1_1") (pintype "unspecified"))
      (node (ref "U7") (pin "12") (pinfunction "Cat1_12") (pintype "unspecified"))
    )
    (net (code "16") (name "A21") (class "Default")
      (node (ref "LED5") (pin "10") (pinfunction "G2_10") (pintype "input"))
      (node (ref "R21") (pin "1") (pinfunction "1_1") (pintype "unspecified"))
      (node (ref "U7") (pin "9") (pinfunction "Cat2_9") (pintype "unspecified"))
    )
    (net (code "17") (name "A31") (class "Default")
      (node (ref "LED5") (pin "11") (pinfunction "G3_11") (pintype "input"))
      (node (ref "R22") (pin "1") (pinfunction "1_1") (pintype "unspecified"))
      (node (ref "U7") (pin "8") (pinfunction "Cat3_8") (pintype "unspecified"))
    )
    (net (code "18") (name "A41") (class "Default")
      (node (ref "LED5") (pin "12") (pinfunction "G4_12") (pintype "input"))
      (node (ref "R23") (pin "1") (pinfunction "1_1") (pintype "unspecified"))
      (node (ref "U7") (pin "6") (pinfunction "Cat4_6") (pintype "unspecified"))
    )
    (net (code "19") (name "ACT1") (class "Default")
      (node (ref "D1") (pin "2") (pinfunction "A_2") (pintype "unspecified"))
      (node (ref "H2") (pin "13") (pinfunction "13_13") (pintype "unspecified"))
      (node (ref "K1") (pin "2") (pinfunction "COIL2_2") (pintype "unspecified"))
      (node (ref "Q2") (pin "3") (pinfunction "3_3") (pintype "input"))
    )
    (net (code "20") (name "ACT2") (class "Default")
      (node (ref "D2") (pin "2") (pinfunction "A_2") (pintype "unspecified"))
      (node (ref "H2") (pin "1") (pinfunction "1_1") (pintype "unspecified"))
      (node (ref "K2") (pin "2") (pinfunction "COIL2_2") (pintype "unspecified"))
      (node (ref "Q1") (pin "3") (pinfunction "3_3") (pintype "input"))
    )
    (net (code "21") (name "B") (class "Default")
      (node (ref "H1") (pin "2") (pinfunction "2_2") (pintype "unspecified"))
      (node (ref "R13") (pin "1") (pinfunction "1_1") (pintype "unspecified"))
      (node (ref "U2") (pin "1") (pinfunction "QB_1") (pintype "unspecified"))
    )
    (net (code "22") (name "B1") (class "Default")
      (node (ref "LED5") (pin "2") (pinfunction "b_2") (pintype "input"))
      (node (ref "R13") (pin "2") (pinfunction "2_2") (pintype "unspecified"))
      (node (ref "U7") (pin "7") (pinfunction "B_7") (pintype "unspecified"))
    )
    (net (code "23") (name "C") (class "Default")
      (node (ref "H1") (pin "3") (pinfunction "3_3") (pintype "unspecified"))
      (node (ref "R14") (pin "1") (pinfunction "1_1") (pintype "unspecified"))
      (node (ref "U2") (pin "2") (pinfunction "QC_2") (pintype "unspecified"))
    )
    (net (code "24") (name "C1") (class "Default")
      (node (ref "LED5") (pin "3") (pinfunction "c_3") (pintype "input"))
      (node (ref "R14") (pin "2") (pinfunction "2_2") (pintype "unspecified"))
      (node (ref "U7") (pin "4") (pinfunction "C_4") (pintype "unspecified"))
    )
    (net (code "25") (name "CLOCK") (class "Default")
      (node (ref "U1") (pin "27") (pinfunction "D2_27") (pintype "bidirectional"))
      (node (ref "U2") (pin "12") (pinfunction "RCLK_12") (pintype "unspecified"))
      (node (ref "U3") (pin "12") (pinfunction "RCLK_12") (pintype "unspecified"))
    )
    (net (code "26") (name "CS") (class "Default")
      (node (ref "H3") (pin "8") (pinfunction "8_8") (pintype "unspecified"))
      (node (ref "U1") (pin "26") (pinfunction "D4_26") (pintype "bidirectional"))
      (node (ref "U13") (pin "1") (pinfunction "CS_1") (pintype "unspecified"))
    )
    (net (code "27") (name "D") (class "Default")
      (node (ref "H1") (pin "4") (pinfunction "4_4") (pintype "unspecified"))
      (node (ref "R15") (pin "1") (pinfunction "1_1") (pintype "unspecified"))
      (node (ref "U2") (pin "3") (pinfunction "QD_3") (pintype "unspecified"))
    )
    (net (code "28") (name "D1") (class "Default")
      (node (ref "LED5") (pin "4") (pinfunction "d_4") (pintype "input"))
      (node (ref "R15") (pin "2") (pinfunction "2_2") (pintype "unspecified"))
      (node (ref "U7") (pin "2") (pinfunction "D_2") (pintype "unspecified"))
    )
    (net (code "29") (name "DATO") (class "Default")
      (node (ref "U1") (pin "28") (pinfunction "D15_28") (pintype "bidirectional"))
      (node (ref "U2") (pin "14") (pinfunction "SER_14") (pintype "unspecified"))
    )
    (net (code "30") (name "DATO2") (class "Default")
      (node (ref "U2") (pin "9") (pinfunction "QH&apos;_9") (pintype "unspecified"))
      (node (ref "U3") (pin "14") (pinfunction "SER_14") (pintype "unspecified"))
    )
    (net (code "31") (name "DP") (class "Default")
      (node (ref "H1") (pin "8") (pinfunction "8_8") (pintype "unspecified"))
      (node (ref "R19") (pin "1") (pinfunction "1_1") (pintype "unspecified"))
      (node (ref "U2") (pin "7") (pinfunction "QH_7") (pintype "unspecified"))
    )
    (net (code "32") (name "DP1") (class "Default")
      (node (ref "LED5") (pin "8") (pinfunction "dp_8") (pintype "input"))
      (node (ref "R19") (pin "2") (pinfunction "2_2") (pintype "unspecified"))
      (node (ref "U7") (pin "3") (pinfunction "DP_3") (pintype "unspecified"))
    )
    (net (code "33") (name "E") (class "Default")
      (node (ref "H1") (pin "5") (pinfunction "5_5") (pintype "unspecified"))
      (node (ref "R16") (pin "1") (pinfunction "1_1") (pintype "unspecified"))
      (node (ref "U2") (pin "4") (pinfunction "QE_4") (pintype "unspecified"))
    )
    (net (code "34") (name "E1") (class "Default")
      (node (ref "LED5") (pin "5") (pinfunction "e_5") (pintype "input"))
      (node (ref "R16") (pin "2") (pinfunction "2_2") (pintype "unspecified"))
      (node (ref "U7") (pin "1") (pinfunction "E_1") (pintype "unspecified"))
    )
    (net (code "35") (name "ESPRX") (class "Default")
      (node (ref "H3") (pin "7") (pinfunction "7_7") (pintype "unspecified"))
      (node (ref "H5") (pin "7") (pinfunction "7_7") (pintype "unspecified"))
      (node (ref "U1") (pin "25") (pinfunction "RX2_25") (pintype "input"))
      (node (ref "U6") (pin "2") (pinfunction "DOUT_2") (pintype "output"))
    )
    (net (code "36") (name "ESPTX") (class "Default")
      (node (ref "H3") (pin "6") (pinfunction "6_6") (pintype "unspecified"))
      (node (ref "H5") (pin "6") (pinfunction "6_6") (pintype "unspecified"))
      (node (ref "U1") (pin "24") (pinfunction "TX2_24") (pintype "output"))
      (node (ref "U6") (pin "3") (pinfunction "DIN_3") (pintype "input"))
    )
    (net (code "37") (name "F") (class "Default")
      (node (ref "H1") (pin "6") (pinfunction "6_6") (pintype "unspecified"))
      (node (ref "R17") (pin "1") (pinfunction "1_1") (pintype "unspecified"))
      (node (ref "U2") (pin "5") (pinfunction "QF_5") (pintype "unspecified"))
    )
    (net (code "38") (name "F1") (class "Default")
      (node (ref "LED5") (pin "6") (pinfunction "f_6") (pintype "input"))
      (node (ref "R17") (pin "2") (pinfunction "2_2") (pintype "unspecified"))
      (node (ref "U7") (pin "10") (pinfunction "F_10") (pintype "unspecified"))
    )
    (net (code "39") (name "G") (class "Default")
      (node (ref "H1") (pin "7") (pinfunction "7_7") (pintype "unspecified"))
      (node (ref "R18") (pin "1") (pinfunction "1_1") (pintype "unspecified"))
      (node (ref "U2") (pin "6") (pinfunction "QG_6") (pintype "unspecified"))
    )
    (net (code "40") (name "G1") (class "Default")
      (node (ref "LED5") (pin "7") (pinfunction "g_7") (pintype "input"))
      (node (ref "R18") (pin "2") (pinfunction "2_2") (pintype "unspecified"))
      (node (ref "U7") (pin "5") (pinfunction "G_5") (pintype "unspecified"))
    )
    (net (code "41") (name "GND") (class "Default")
      (node (ref "C1") (pin "1") (pinfunction "1_1") (pintype "input"))
      (node (ref "C2") (pin "1") (pinfunction "1_1") (pintype "input"))
      (node (ref "C3") (pin "1") (pinfunction "1_1") (pintype "input"))
      (node (ref "C4") (pin "1") (pinfunction "1_1") (pintype "input"))
      (node (ref "C5") (pin "1") (pinfunction "1_1") (pintype "input"))
      (node (ref "C6") (pin "2") (pinfunction "2_2") (pintype "unspecified"))
      (node (ref "C7") (pin "1") (pinfunction "1_1") (pintype "unspecified"))
      (node (ref "CN1") (pin "3") (pinfunction "3_3") (pintype "unspecified"))
      (node (ref "CN2") (pin "3") (pinfunction "3_3") (pintype "unspecified"))
      (node (ref "H1") (pin "13") (pinfunction "13_13") (pintype "unspecified"))
      (node (ref "H2") (pin "7") (pinfunction "7_7") (pintype "unspecified"))
      (node (ref "H3") (pin "13") (pinfunction "13_13") (pintype "unspecified"))
      (node (ref "H4") (pin "7") (pinfunction "7_7") (pintype "unspecified"))
      (node (ref "H5") (pin "13") (pinfunction "13_13") (pintype "unspecified"))
      (node (ref "J1") (pin "2") (pinfunction "CDN_2") (pintype "bidirectional"))
      (node (ref "J1") (pin "3") (pinfunction "-_3") (pintype "bidirectional"))
      (node (ref "LED1") (pin "1") (pinfunction "-_1") (pintype "unspecified"))
      (node (ref "LED2") (pin "1") (pinfunction "-_1") (pintype "unspecified"))
      (node (ref "LED3") (pin "1") (pinfunction "-_1") (pintype "unspecified"))
      (node (ref "LED4") (pin "1") (pinfunction "-_1") (pintype "unspecified"))
      (node (ref "Q1") (pin "2") (pinfunction "2_2") (pintype "input"))
      (node (ref "Q2") (pin "2") (pinfunction "2_2") (pintype "input"))
      (node (ref "Q3") (pin "2") (pinfunction "2_2") (pintype "input"))
      (node (ref "Q4") (pin "2") (pinfunction "2_2") (pintype "input"))
      (node (ref "Q5") (pin "2") (pinfunction "2_2") (pintype "input"))
      (node (ref "Q6") (pin "2") (pinfunction "2_2") (pintype "input"))
      (node (ref "R29") (pin "1") (pinfunction "1_1") (pintype "unspecified"))
      (node (ref "R4") (pin "1") (pinfunction "1_1") (pintype "input"))
      (node (ref "R5") (pin "2") (pinfunction "2_2") (pintype "input"))
      (node (ref "RELAY3") (pin "2") (pinfunction "2_2") (pintype "unspecified"))
      (node (ref "U1") (pin "2") (pinfunction "GND_2") (pintype "passive"))
      (node (ref "U1") (pin "29") (pinfunction "GND_29") (pintype "passive"))
      (node (ref "U10") (pin "2") (pinfunction "GND_2") (pintype "passive"))
      (node (ref "U11") (pin "4") (pinfunction "GND_4") (pintype "unspecified"))
      (node (ref "U12") (pin "2") (pinfunction "GND_2") (pintype "unspecified"))
      (node (ref "U13") (pin "6") (pinfunction "GND_6") (pintype "unspecified"))
      (node (ref "U2") (pin "10") (pinfunction "SRCLR#_10") (pintype "unspecified"))
      (node (ref "U2") (pin "8") (pinfunction "GND_8") (pintype "unspecified"))
      (node (ref "U3") (pin "10") (pinfunction "SRCLR#_10") (pintype "unspecified"))
      (node (ref "U3") (pin "8") (pinfunction "GND_8") (pintype "unspecified"))
      (node (ref "U4") (pin "2") (pinfunction "CAT_2") (pintype "unspecified"))
      (node (ref "U5") (pin "2") (pinfunction "CAT_2") (pintype "unspecified"))
      (node (ref "U6") (pin "10") (pinfunction "GND_10") (pintype "unspecified"))
      (node (ref "U8") (pin "2") (pinfunction "GND_2") (pintype "unspecified"))
      (node (ref "U9") (pin "2") (pinfunction "-IN_2") (pintype "unspecified"))
      (node (ref "U9") (pin "6") (pinfunction "OUT-_6") (pintype "unspecified"))
    )
    (net (code "42") (name "LATCH") (class "Default")
      (node (ref "U1") (pin "6") (pinfunction "D27_6") (pintype "bidirectional"))
      (node (ref "U2") (pin "11") (pinfunction "SRCLK_11") (pintype "unspecified"))
      (node (ref "U3") (pin "11") (pinfunction "SRCLK_11") (pintype "unspecified"))
    )
    (net (code "43") (name "LED_BLUE") (class "Default")
      (node (ref "H2") (pin "10") (pinfunction "10_10") (pintype "unspecified"))
      (node (ref "R26") (pin "1") (pinfunction "1_1") (pintype "input"))
      (node (ref "U1") (pin "7") (pinfunction "D26_7") (pintype "bidirectional"))
    )
    (net (code "44") (name "LED_WIFI") (class "Default")
      (node (ref "H2") (pin "9") (pinfunction "9_9") (pintype "unspecified"))
      (node (ref "R25") (pin "1") (pinfunction "1_1") (pintype "input"))
      (node (ref "U1") (pin "8") (pinfunction "D25_8") (pintype "bidirectional"))
    )
    (net (code "45") (name "MISO") (class "Default")
      (node (ref "H3") (pin "3") (pinfunction "3_3") (pintype "unspecified"))
      (node (ref "U1") (pin "21") (pinfunction "D19_21") (pintype "bidirectional"))
      (node (ref "U13") (pin "4") (pinfunction "MISO_4") (pintype "unspecified"))
    )
    (net (code "46") (name "MON") (class "Default")
      (node (ref "R29") (pin "2") (pinfunction "2_2") (pintype "unspecified"))
      (node (ref "R30") (pin "1") (pinfunction "1_1") (pintype "input"))
      (node (ref "U1") (pin "20") (pinfunction "D21_20") (pintype "bidirectional"))
    )
    (net (code "47") (name "MOSI") (class "Default")
      (node (ref "H3") (pin "2") (pinfunction "2_2") (pintype "unspecified"))
      (node (ref "U1") (pin "16") (pinfunction "D23_16") (pintype "bidirectional"))
      (node (ref "U13") (pin "3") (pinfunction "MOSI_3") (pintype "unspecified"))
    )
    (net (code "48") (name "Net-(K1-MAIN)") (class "Default")
      (node (ref "K1") (pin "1") (pinfunction "MAIN_1") (pintype "unspecified"))
      (node (ref "RELAY1") (pin "2") (pinfunction "2_2") (pintype "unspecified"))
    )
    (net (code "49") (name "Net-(K1-NC)") (class "Default")
      (node (ref "K1") (pin "4") (pinfunction "NC_4") (pintype "unspecified"))
      (node (ref "RELAY1") (pin "1") (pinfunction "1_1") (pintype "unspecified"))
    )
    (net (code "50") (name "Net-(K1-NO)") (class "Default")
      (node (ref "K1") (pin "3") (pinfunction "NO_3") (pintype "unspecified"))
      (node (ref "RELAY4") (pin "1") (pinfunction "1_1") (pintype "unspecified"))
    )
    (net (code "51") (name "Net-(K2-MAIN)") (class "Default")
      (node (ref "K2") (pin "1") (pinfunction "MAIN_1") (pintype "unspecified"))
      (node (ref "RELAY2") (pin "1") (pinfunction "1_1") (pintype "unspecified"))
    )
    (net (code "52") (name "Net-(K2-NC)") (class "Default")
      (node (ref "K2") (pin "4") (pinfunction "NC_4") (pintype "unspecified"))
      (node (ref "RELAY4") (pin "2") (pinfunction "2_2") (pintype "unspecified"))
    )
    (net (code "53") (name "Net-(K2-NO)") (class "Default")
      (node (ref "K2") (pin "3") (pinfunction "NO_3") (pintype "unspecified"))
      (node (ref "RELAY2") (pin "2") (pinfunction "2_2") (pintype "unspecified"))
    )
    (net (code "54") (name "Net-(LED1-+)") (class "Default")
      (node (ref "LED1") (pin "2") (pinfunction "+_2") (pintype "unspecified"))
      (node (ref "R24") (pin "2") (pinfunction "2_2") (pintype "input"))
    )
    (net (code "55") (name "Net-(LED2-+)") (class "Default")
      (node (ref "LED2") (pin "2") (pinfunction "+_2") (pintype "unspecified"))
      (node (ref "R25") (pin "2") (pinfunction "2_2") (pintype "input"))
    )
    (net (code "56") (name "Net-(LED3-+)") (class "Default")
      (node (ref "LED3") (pin "2") (pinfunction "+_2") (pintype "unspecified"))
      (node (ref "R26") (pin "2") (pinfunction "2_2") (pintype "input"))
    )
    (net (code "57") (name "Net-(LED4-+)") (class "Default")
      (node (ref "LED4") (pin "2") (pinfunction "+_2") (pintype "unspecified"))
      (node (ref "R31") (pin "2") (pinfunction "2_2") (pintype "input"))
    )
    (net (code "58") (name "Net-(Q1-Pad1)") (class "Default")
      (node (ref "Q1") (pin "1") (pinfunction "1_1") (pintype "input"))
      (node (ref "R5") (pin "1") (pinfunction "1_1") (pintype "input"))
      (node (ref "R7") (pin "2") (pinfunction "2_2") (pintype "unspecified"))
    )
    (net (code "59") (name "Net-(Q2-Pad1)") (class "Default")
      (node (ref "Q2") (pin "1") (pinfunction "1_1") (pintype "input"))
      (node (ref "R4") (pin "2") (pinfunction "2_2") (pintype "input"))
      (node (ref "R6") (pin "2") (pinfunction "2_2") (pintype "unspecified"))
    )
    (net (code "60") (name "Net-(Q3-Pad1)") (class "Default")
      (node (ref "Q3") (pin "1") (pinfunction "1_1") (pintype "input"))
      (node (ref "R8") (pin "2") (pinfunction "2_2") (pintype "input"))
    )
    (net (code "61") (name "Net-(Q4-Pad1)") (class "Default")
      (node (ref "Q4") (pin "1") (pinfunction "1_1") (pintype "input"))
      (node (ref "R9") (pin "2") (pinfunction "2_2") (pintype "input"))
    )
    (net (code "62") (name "Net-(Q5-Pad1)") (class "Default")
      (node (ref "Q5") (pin "1") (pinfunction "1_1") (pintype "input"))
      (node (ref "R10") (pin "2") (pinfunction "2_2") (pintype "input"))
    )
    (net (code "63") (name "Net-(Q6-Pad1)") (class "Default")
      (node (ref "Q6") (pin "1") (pinfunction "1_1") (pintype "input"))
      (node (ref "R11") (pin "2") (pinfunction "2_2") (pintype "input"))
    )
    (net (code "64") (name "Net-(U1-3V3)") (class "Default")
      (node (ref "R27") (pin "1") (pinfunction "1_1") (pintype "input"))
      (node (ref "U1") (pin "30") (pinfunction "3V3_30") (pintype "unspecified"))
    )
    (net (code "65") (name "Net-(U4-AN)") (class "Default")
      (node (ref "R2") (pin "2") (pinfunction "2_2") (pintype "input"))
      (node (ref "U4") (pin "1") (pinfunction "AN_1") (pintype "unspecified"))
    )
    (net (code "66") (name "Net-(U4-EMI)") (class "Default")
      (node (ref "R6") (pin "1") (pinfunction "1_1") (pintype "unspecified"))
      (node (ref "U4") (pin "3") (pinfunction "EMI_3") (pintype "unspecified"))
    )
    (net (code "67") (name "Net-(U5-AN)") (class "Default")
      (node (ref "R3") (pin "2") (pinfunction "2_2") (pintype "input"))
      (node (ref "U5") (pin "1") (pinfunction "AN_1") (pintype "unspecified"))
    )
    (net (code "68") (name "Net-(U5-EMI)") (class "Default")
      (node (ref "R7") (pin "1") (pinfunction "1_1") (pintype "unspecified"))
      (node (ref "U5") (pin "3") (pinfunction "EMI_3") (pintype "unspecified"))
    )
    (net (code "69") (name "Net-(U6-PWM0RSSI)") (class "Default")
      (node (ref "R31") (pin "1") (pinfunction "1_1") (pintype "input"))
      (node (ref "U6") (pin "6") (pinfunction "PWM0RSSI_6") (pintype "output"))
    )
    (net (code "70") (name "Net-(U9-B+)") (class "Default")
      (node (ref "BT1") (pin "1") (pinfunction "1_1") (pintype "unspecified"))
      (node (ref "BT1") (pin "2") (pinfunction "2_2") (pintype "unspecified"))
      (node (ref "BT1") (pin "3") (pinfunction "3_3") (pintype "unspecified"))
      (node (ref "U9") (pin "3") (pinfunction "B+_3") (pintype "unspecified"))
    )
    (net (code "71") (name "Net-(U9-B-)") (class "Default")
      (node (ref "BT2") (pin "1") (pinfunction "1_1") (pintype "unspecified"))
      (node (ref "BT2") (pin "2") (pinfunction "2_2") (pintype "unspecified"))
      (node (ref "BT2") (pin "3") (pinfunction "3_3") (pintype "unspecified"))
      (node (ref "U9") (pin "4") (pinfunction "B-_4") (pintype "unspecified"))
    )
    (net (code "72") (name "OUT_COOL") (class "Default")
      (node (ref "H2") (pin "3") (pinfunction "3_3") (pintype "unspecified"))
      (node (ref "R3") (pin "1") (pinfunction "1_1") (pintype "input"))
      (node (ref "U1") (pin "10") (pinfunction "D32_10") (pintype "bidirectional"))
    )
    (net (code "73") (name "OUT_HEAT") (class "Default")
      (node (ref "H2") (pin "11") (pinfunction "11_11") (pintype "unspecified"))
      (node (ref "R2") (pin "1") (pinfunction "1_1") (pintype "input"))
      (node (ref "U1") (pin "9") (pinfunction "D33_9") (pintype "bidirectional"))
    )
    (net (code "74") (name "SALIDA1") (class "Default")
      (node (ref "H3") (pin "5") (pinfunction "5_5") (pintype "unspecified"))
      (node (ref "SW1") (pin "1") (pinfunction "1_1") (pintype "unspecified"))
      (node (ref "SW1") (pin "2") (pinfunction "2_2") (pintype "unspecified"))
      (node (ref "U1") (pin "23") (pinfunction "D5_23") (pintype "bidirectional"))
    )
    (net (code "75") (name "SALIDA2") (class "Default")
      (node (ref "H3") (pin "9") (pinfunction "9_9") (pintype "unspecified"))
      (node (ref "SW1") (pin "3") (pinfunction "3_3") (pintype "unspecified"))
      (node (ref "U1") (pin "17") (pinfunction "D22_17") (pintype "bidirectional"))
    )
    (net (code "76") (name "SCK") (class "Default")
      (node (ref "H3") (pin "4") (pinfunction "4_4") (pintype "unspecified"))
      (node (ref "U1") (pin "22") (pinfunction "D18_22") (pintype "bidirectional"))
      (node (ref "U13") (pin "2") (pinfunction "SCK_2") (pintype "unspecified"))
    )
    (net (code "77") (name "SENSOR") (class "Default")
      (node (ref "CN2") (pin "2") (pinfunction "2_2") (pintype "unspecified"))
      (node (ref "R28") (pin "1") (pinfunction "1_1") (pintype "input"))
      (node (ref "SW1") (pin "6") (pinfunction "6_6") (pintype "unspecified"))
      (node (ref "SW1") (pin "7") (pinfunction "7_7") (pintype "unspecified"))
    )
    (net (code "78") (name "SENSOR2") (class "Default")
      (node (ref "CN1") (pin "2") (pinfunction "2_2") (pintype "unspecified"))
      (node (ref "R1") (pin "1") (pinfunction "1_1") (pintype "input"))
      (node (ref "SW1") (pin "8") (pinfunction "8_8") (pintype "unspecified"))
    )
    (net (code "79") (name "unconnected-(H2-Pad4)") (class "Default")
      (node (ref "H2") (pin "4") (pinfunction "4_4") (pintype "unspecified"))
    )
    (net (code "80") (name "unconnected-(H2-Pad5)") (class "Default")
      (node (ref "H2") (pin "5") (pinfunction "5_5") (pintype "unspecified"))
    )
    (net (code "81") (name "unconnected-(H2-Pad6)") (class "Default")
      (node (ref "H2") (pin "6") (pinfunction "6_6") (pintype "unspecified"))
    )
    (net (code "82") (name "unconnected-(H2-Pad8)") (class "Default")
      (node (ref "H2") (pin "8") (pinfunction "8_8") (pintype "unspecified"))
    )
    (net (code "83") (name "unconnected-(H3-Pad10)") (class "Default")
      (node (ref "H3") (pin "10") (pinfunction "10_10") (pintype "unspecified"))
    )
    (net (code "84") (name "unconnected-(H3-Pad11)") (class "Default")
      (node (ref "H3") (pin "11") (pinfunction "11_11") (pintype "unspecified"))
    )
    (net (code "85") (name "unconnected-(H3-Pad12)") (class "Default")
      (node (ref "H3") (pin "12") (pinfunction "12_12") (pintype "unspecified"))
    )
    (net (code "86") (name "unconnected-(H4-Pad1)") (class "Default")
      (node (ref "H4") (pin "1") (pinfunction "1_1") (pintype "unspecified"))
    )
    (net (code "87") (name "unconnected-(H4-Pad2)") (class "Default")
      (node (ref "H4") (pin "2") (pinfunction "2_2") (pintype "unspecified"))
    )
    (net (code "88") (name "unconnected-(H4-Pad3)") (class "Default")
      (node (ref "H4") (pin "3") (pinfunction "3_3") (pintype "unspecified"))
    )
    (net (code "89") (name "unconnected-(H4-Pad4)") (class "Default")
      (node (ref "H4") (pin "4") (pinfunction "4_4") (pintype "unspecified"))
    )
    (net (code "90") (name "unconnected-(H4-Pad5)") (class "Default")
      (node (ref "H4") (pin "5") (pinfunction "5_5") (pintype "unspecified"))
    )
    (net (code "91") (name "unconnected-(H4-Pad6)") (class "Default")
      (node (ref "H4") (pin "6") (pinfunction "6_6") (pintype "unspecified"))
    )
    (net (code "92") (name "unconnected-(H4-Pad8)") (class "Default")
      (node (ref "H4") (pin "8") (pinfunction "8_8") (pintype "unspecified"))
    )
    (net (code "93") (name "unconnected-(H4-Pad9)") (class "Default")
      (node (ref "H4") (pin "9") (pinfunction "9_9") (pintype "unspecified"))
    )
    (net (code "94") (name "unconnected-(H4-Pad10)") (class "Default")
      (node (ref "H4") (pin "10") (pinfunction "10_10") (pintype "unspecified"))
    )
    (net (code "95") (name "unconnected-(H4-Pad11)") (class "Default")
      (node (ref "H4") (pin "11") (pinfunction "11_11") (pintype "unspecified"))
    )
    (net (code "96") (name "unconnected-(H4-Pad12)") (class "Default")
      (node (ref "H4") (pin "12") (pinfunction "12_12") (pintype "unspecified"))
    )
    (net (code "97") (name "unconnected-(H4-Pad13)") (class "Default")
      (node (ref "H4") (pin "13") (pinfunction "13_13") (pintype "unspecified"))
    )
    (net (code "98") (name "unconnected-(H5-Pad2)") (class "Default")
      (node (ref "H5") (pin "2") (pinfunction "2_2") (pintype "unspecified"))
    )
    (net (code "99") (name "unconnected-(H5-Pad3)") (class "Default")
      (node (ref "H5") (pin "3") (pinfunction "3_3") (pintype "unspecified"))
    )
    (net (code "100") (name "unconnected-(H5-Pad4)") (class "Default")
      (node (ref "H5") (pin "4") (pinfunction "4_4") (pintype "unspecified"))
    )
    (net (code "101") (name "unconnected-(H5-Pad5)") (class "Default")
      (node (ref "H5") (pin "5") (pinfunction "5_5") (pintype "unspecified"))
    )
    (net (code "102") (name "unconnected-(H5-Pad8)") (class "Default")
      (node (ref "H5") (pin "8") (pinfunction "8_8") (pintype "unspecified"))
    )
    (net (code "103") (name "unconnected-(H5-Pad9)") (class "Default")
      (node (ref "H5") (pin "9") (pinfunction "9_9") (pintype "unspecified"))
    )
    (net (code "104") (name "unconnected-(H5-Pad10)") (class "Default")
      (node (ref "H5") (pin "10") (pinfunction "10_10") (pintype "unspecified"))
    )
    (net (code "105") (name "unconnected-(H5-Pad11)") (class "Default")
      (node (ref "H5") (pin "11") (pinfunction "11_11") (pintype "unspecified"))
    )
    (net (code "106") (name "unconnected-(H5-Pad12)") (class "Default")
      (node (ref "H5") (pin "12") (pinfunction "12_12") (pintype "unspecified"))
    )
    (net (code "107") (name "unconnected-(SW1-Pad4)") (class "Default")
      (node (ref "SW1") (pin "4") (pinfunction "4_4") (pintype "unspecified"))
    )
    (net (code "108") (name "unconnected-(SW1-Pad5)") (class "Default")
      (node (ref "SW1") (pin "5") (pinfunction "5_5") (pintype "unspecified"))
    )
    (net (code "109") (name "unconnected-(U1-D12-Pad4)") (class "Default")
      (node (ref "U1") (pin "4") (pinfunction "D12_4") (pintype "bidirectional"))
    )
    (net (code "110") (name "unconnected-(U1-D13-Pad3)") (class "Default")
      (node (ref "U1") (pin "3") (pinfunction "D13_3") (pintype "bidirectional"))
    )
    (net (code "111") (name "unconnected-(U1-D14-Pad5)") (class "Default")
      (node (ref "U1") (pin "5") (pinfunction "D14_5") (pintype "bidirectional"))
    )
    (net (code "112") (name "unconnected-(U1-D34-Pad12)") (class "Default")
      (node (ref "U1") (pin "12") (pinfunction "D34_12") (pintype "bidirectional"))
    )
    (net (code "113") (name "unconnected-(U1-D35-Pad11)") (class "Default")
      (node (ref "U1") (pin "11") (pinfunction "D35_11") (pintype "bidirectional"))
    )
    (net (code "114") (name "unconnected-(U1-EN-Pad15)") (class "Default")
      (node (ref "U1") (pin "15") (pinfunction "EN_15") (pintype "unspecified"))
    )
    (net (code "115") (name "unconnected-(U1-RX0-Pad19)") (class "Default")
      (node (ref "U1") (pin "19") (pinfunction "RX0_19") (pintype "input"))
    )
    (net (code "116") (name "unconnected-(U1-TX0-Pad18)") (class "Default")
      (node (ref "U1") (pin "18") (pinfunction "TX0_18") (pintype "output"))
    )
    (net (code "117") (name "unconnected-(U1-VIN-Pad1)") (class "Default")
      (node (ref "U1") (pin "1") (pinfunction "VIN_1") (pintype "passive"))
    )
    (net (code "118") (name "unconnected-(U1-VN-Pad13)") (class "Default")
      (node (ref "U1") (pin "13") (pinfunction "VN_13") (pintype "bidirectional"))
    )
    (net (code "119") (name "unconnected-(U1-VP-Pad14)") (class "Default")
      (node (ref "U1") (pin "14") (pinfunction "VP_14") (pintype "bidirectional"))
    )
    (net (code "120") (name "unconnected-(U3-QE-Pad4)") (class "Default")
      (node (ref "U3") (pin "4") (pinfunction "QE_4") (pintype "unspecified"))
    )
    (net (code "121") (name "unconnected-(U3-QF-Pad5)") (class "Default")
      (node (ref "U3") (pin "5") (pinfunction "QF_5") (pintype "unspecified"))
    )
    (net (code "122") (name "unconnected-(U3-QG-Pad6)") (class "Default")
      (node (ref "U3") (pin "6") (pinfunction "QG_6") (pintype "unspecified"))
    )
    (net (code "123") (name "unconnected-(U3-QH&apos;-Pad9)") (class "Default")
      (node (ref "U3") (pin "9") (pinfunction "QH&apos;_9") (pintype "unspecified"))
    )
    (net (code "124") (name "unconnected-(U3-QH-Pad7)") (class "Default")
      (node (ref "U3") (pin "7") (pinfunction "QH_7") (pintype "unspecified"))
    )
    (net (code "125") (name "unconnected-(U6-AD0DIO0-Pad20)") (class "Default")
      (node (ref "U6") (pin "20") (pinfunction "AD0DIO0_20") (pintype "unspecified"))
    )
    (net (code "126") (name "unconnected-(U6-AD1DIO1-Pad19)") (class "Default")
      (node (ref "U6") (pin "19") (pinfunction "AD1DIO1_19") (pintype "unspecified"))
    )
    (net (code "127") (name "unconnected-(U6-AD2DIO2-Pad18)") (class "Default")
      (node (ref "U6") (pin "18") (pinfunction "AD2DIO2_18") (pintype "unspecified"))
    )
    (net (code "128") (name "unconnected-(U6-AD3DIO3-Pad17)") (class "Default")
      (node (ref "U6") (pin "17") (pinfunction "AD3DIO3_17") (pintype "unspecified"))
    )
    (net (code "129") (name "unconnected-(U6-AD4DIO4-Pad11)") (class "Default")
      (node (ref "U6") (pin "11") (pinfunction "AD4DIO4_11") (pintype "unspecified"))
    )
    (net (code "130") (name "unconnected-(U6-ASCAD5DIO5-Pad15)") (class "Default")
      (node (ref "U6") (pin "15") (pinfunction "ASCAD5DIO5_15") (pintype "unspecified"))
    )
    (net (code "131") (name "unconnected-(U6-CTSDIO7-Pad12)") (class "Default")
      (node (ref "U6") (pin "12") (pinfunction "CTSDIO7_12") (pintype "unspecified"))
    )
    (net (code "132") (name "unconnected-(U6-DO8-Pad4)") (class "Default")
      (node (ref "U6") (pin "4") (pinfunction "DO8_4") (pintype "output"))
    )
    (net (code "133") (name "unconnected-(U6-DTRDI8-Pad9)") (class "Default")
      (node (ref "U6") (pin "9") (pinfunction "DTRDI8_9") (pintype "input"))
    )
    (net (code "134") (name "unconnected-(U6-ONSLEEP-Pad13)") (class "Default")
      (node (ref "U6") (pin "13") (pinfunction "ONSLEEP_13") (pintype "output"))
    )
    (net (code "135") (name "unconnected-(U6-PWM1-Pad7)") (class "Default")
      (node (ref "U6") (pin "7") (pinfunction "PWM1_7") (pintype "output"))
    )
    (net (code "136") (name "unconnected-(U6-RESERVED-Pad8)") (class "Default")
      (node (ref "U6") (pin "8") (pinfunction "RESERVED_8") (pintype "unspecified"))
    )
    (net (code "137") (name "unconnected-(U6-RESET-Pad5)") (class "Default")
      (node (ref "U6") (pin "5") (pinfunction "RESET_5") (pintype "input"))
    )
    (net (code "138") (name "unconnected-(U6-RTSAD6DIO6-Pad16)") (class "Default")
      (node (ref "U6") (pin "16") (pinfunction "RTSAD6DIO6_16") (pintype "unspecified"))
    )
    (net (code "139") (name "unconnected-(U6-VREF-Pad14)") (class "Default")
      (node (ref "U6") (pin "14") (pinfunction "VREF_14") (pintype "input"))
    )
  )
)
